# Detection_Circuit_Sheet_02.net
KiCad netlist of a schematic drawn in Altium Designer
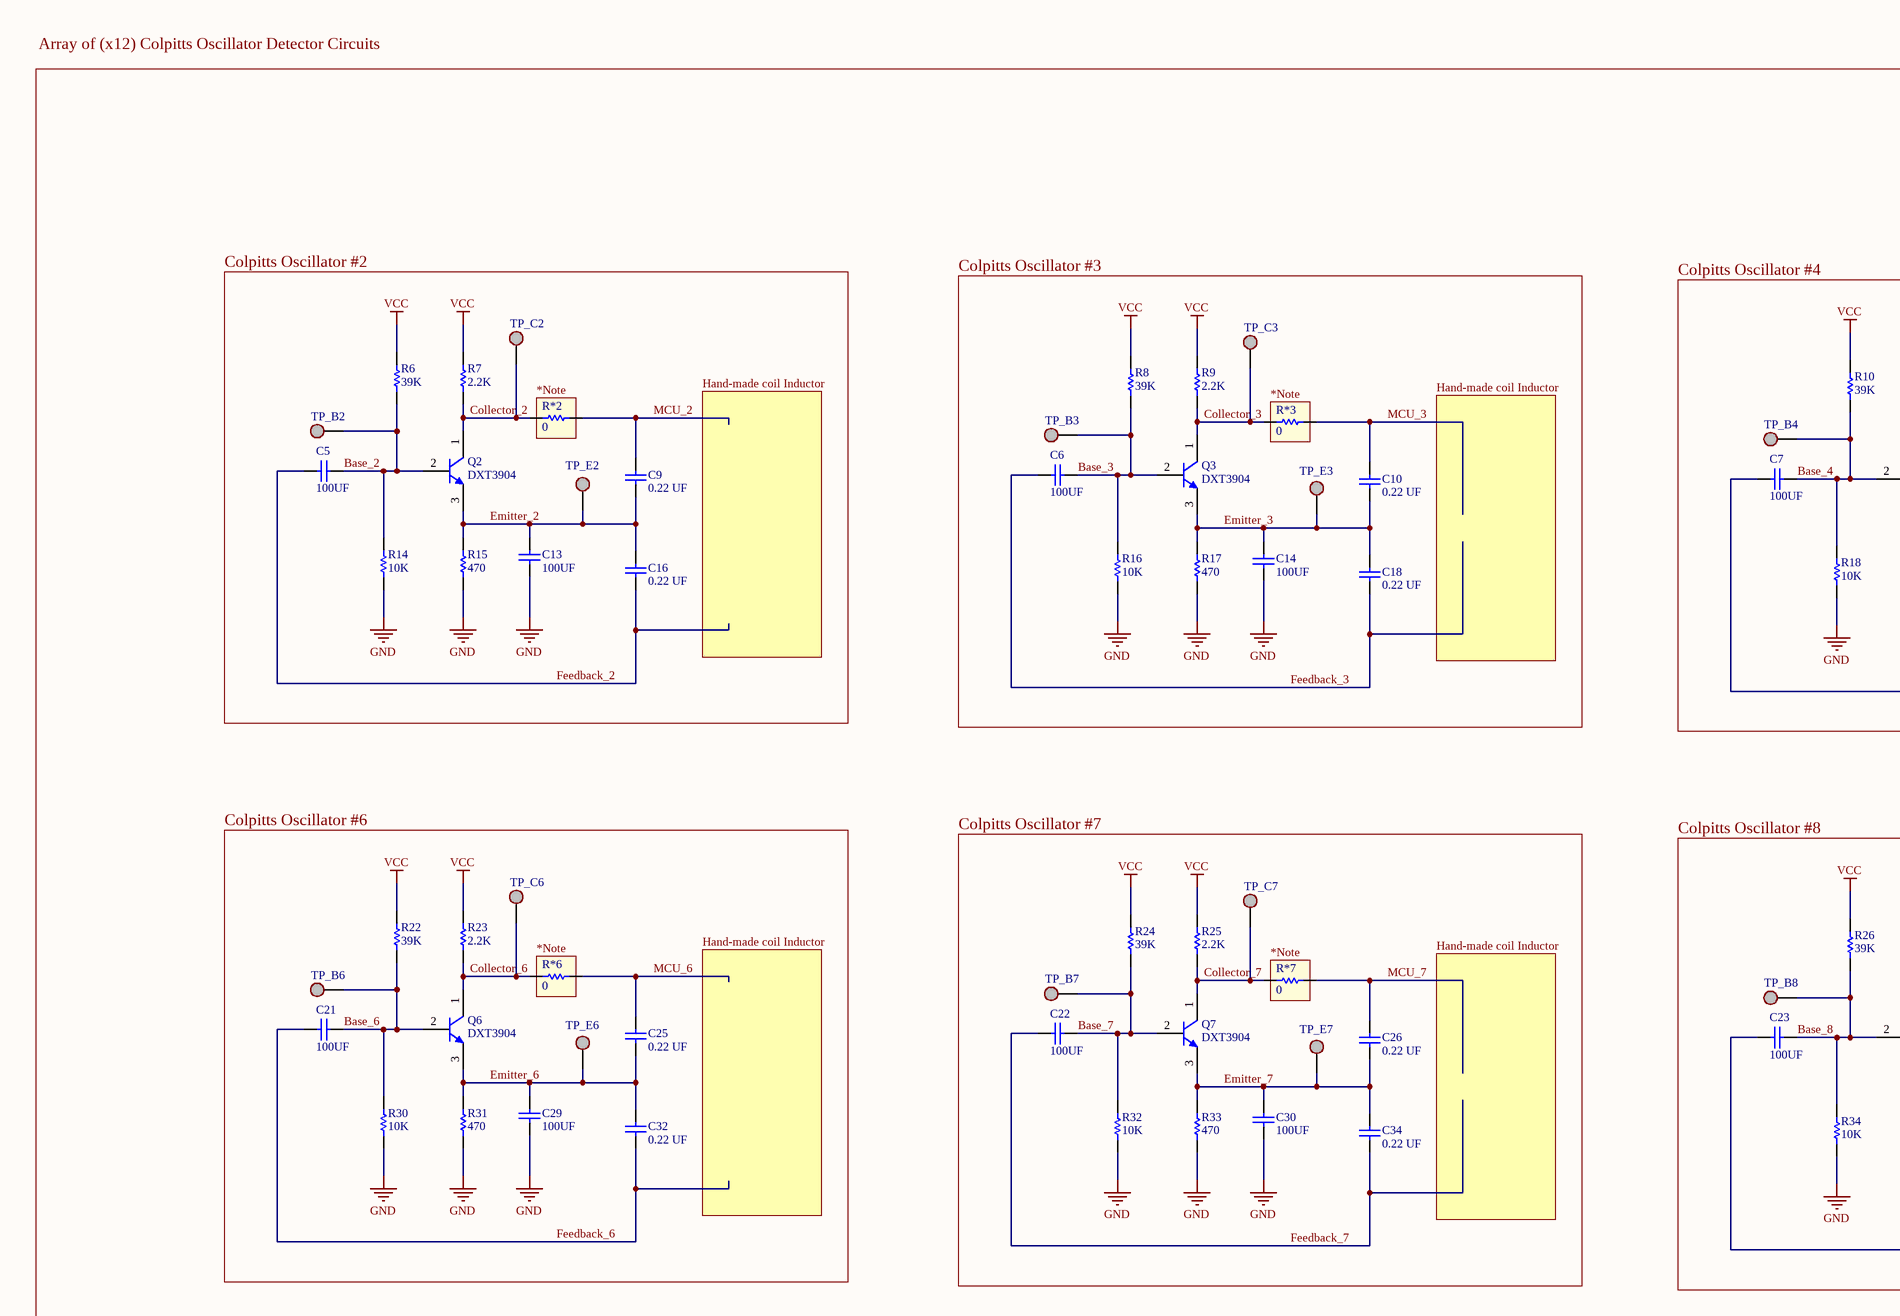
[diagram p0: Detection_Circuit_Sheet_02.SchDoc, top left]
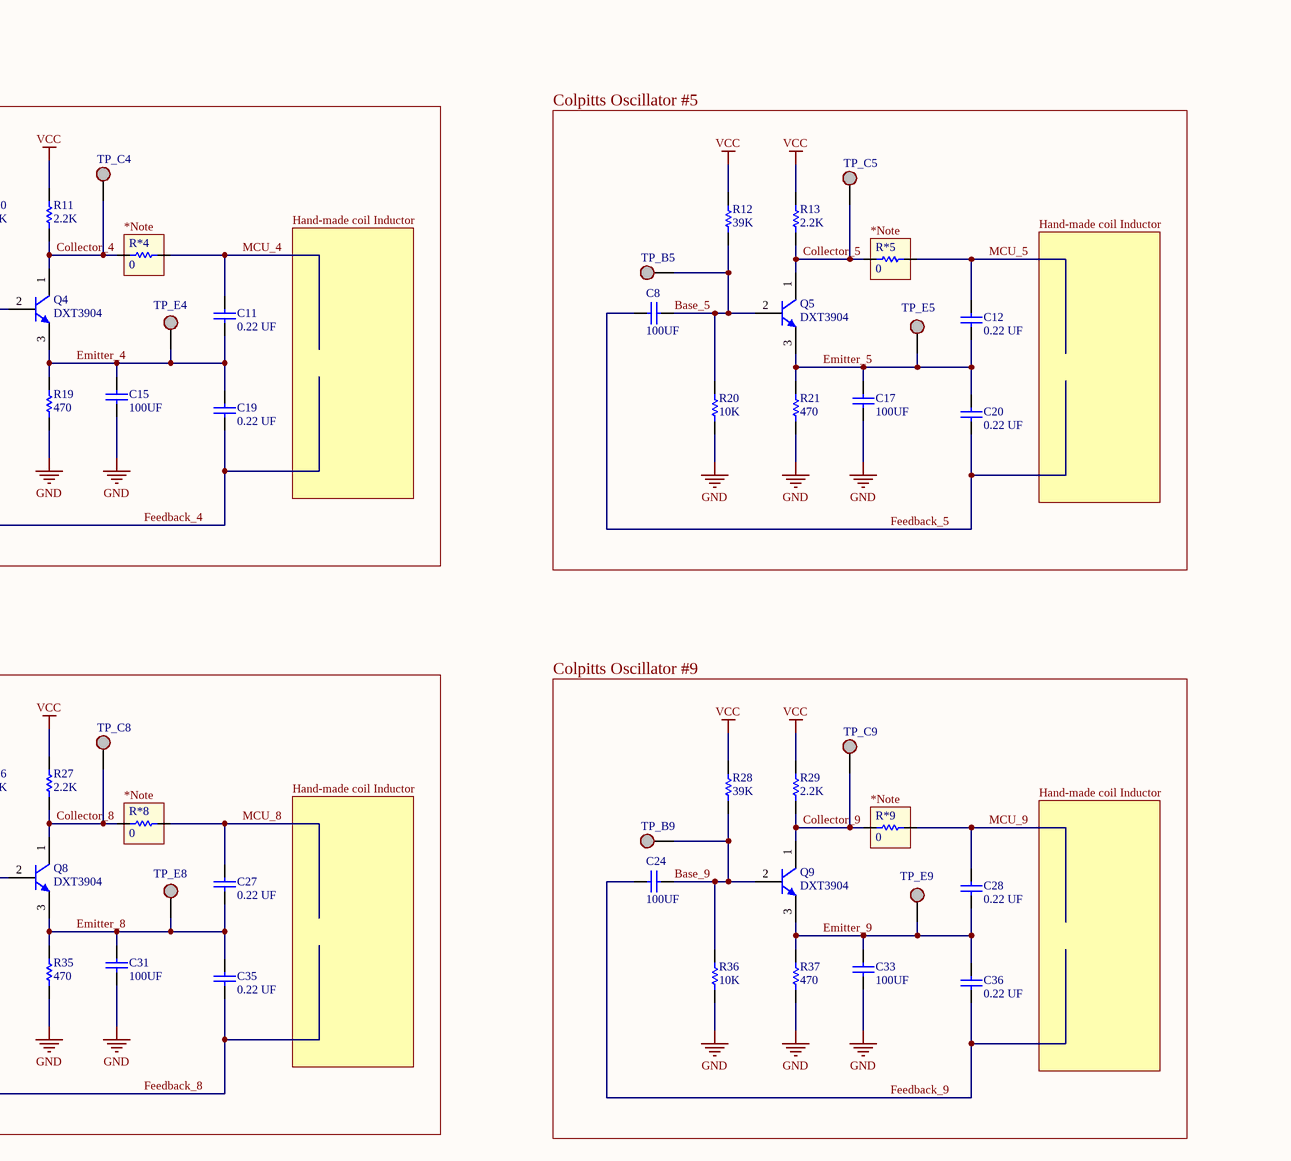
[diagram p1: Detection_Circuit_Sheet_02.SchDoc, top right]
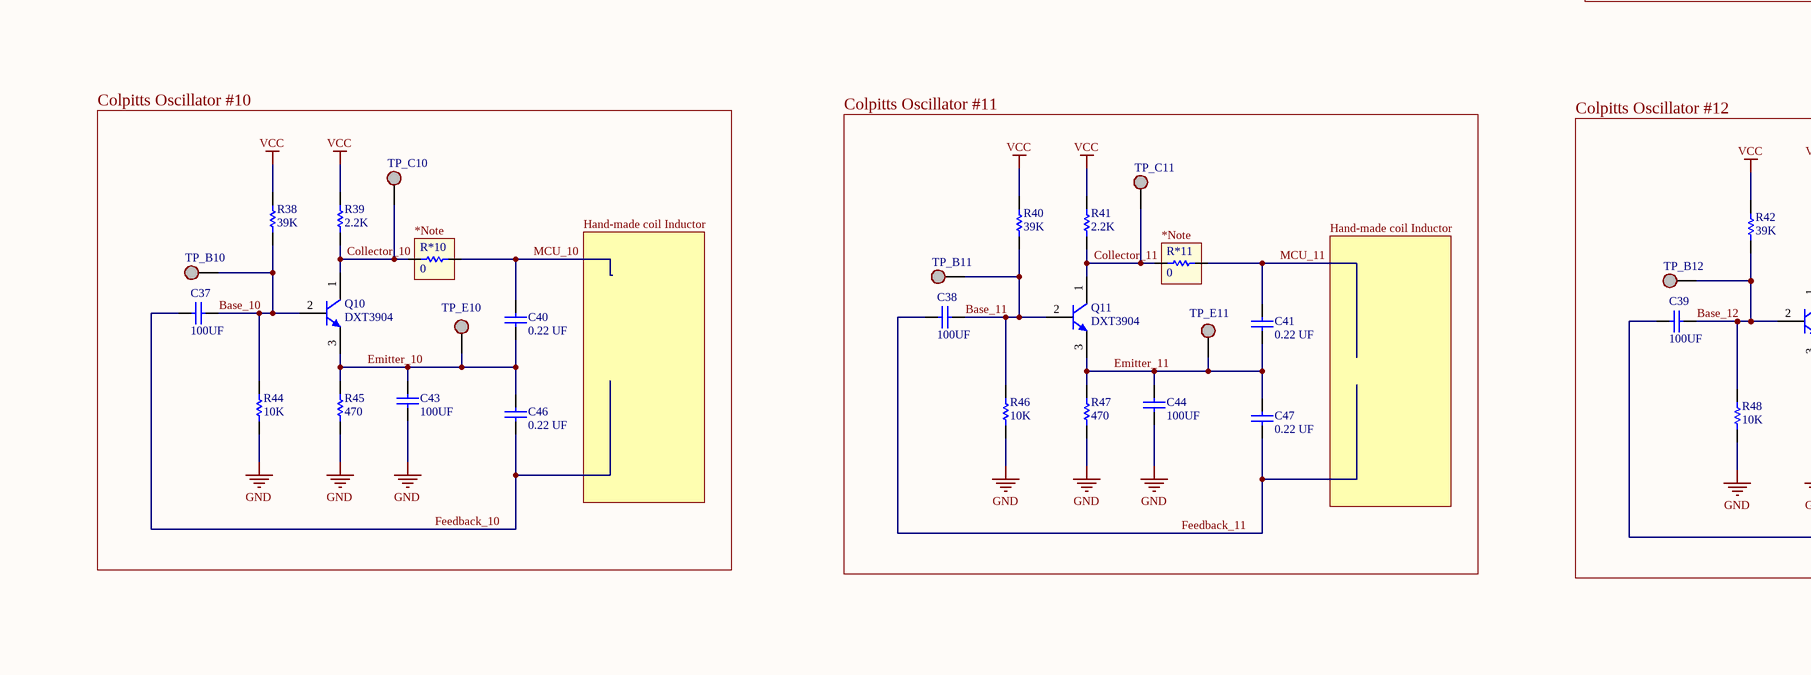
[diagram p2: Detection_Circuit_Sheet_02.SchDoc, bottom left]
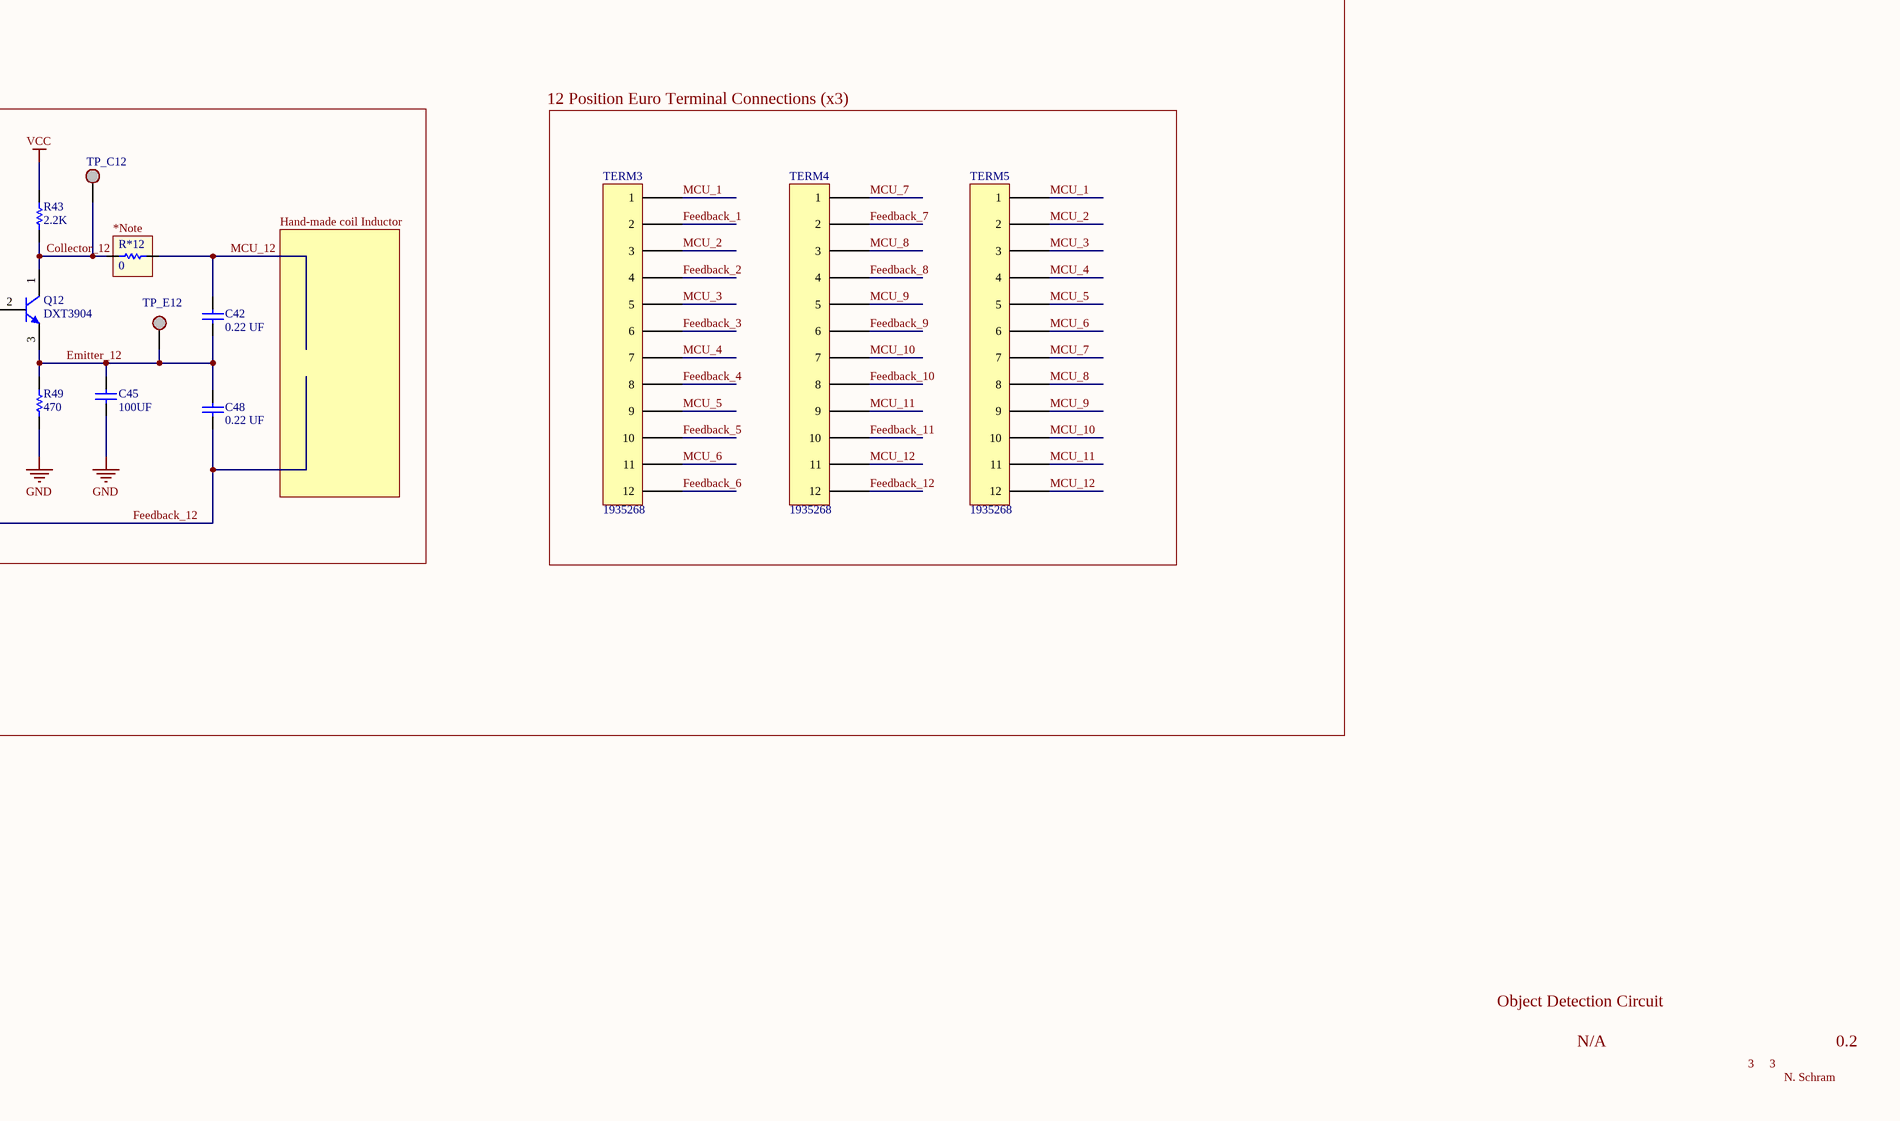
[diagram p3: Detection_Circuit_Sheet_02.SchDoc, bottom right]

(export (version "E")
  (design (tool "Eeschema 10.0.6"))
  (components
    (comp (ref "C5")
      (value "100UF")
      (footprint "C1210_M")
      (description "CAP CER 100UF 16V X5R 1210")
      (fields (field (name "MANUFACTURER PART NUMBER") "CC1210MKX5R7BB107") (field (name "TOLERANCE") "±20%"))
      (libsource (lib "CC1210MKX5R7BB107") (part "CC1210MKX5R7BB107"))
    )
    (comp (ref "C6")
      (value "100UF")
      (footprint "C1210_M")
      (description "CAP CER 100UF 16V X5R 1210")
      (fields (field (name "MANUFACTURER PART NUMBER") "CC1210MKX5R7BB107") (field (name "TOLERANCE") "±20%"))
      (libsource (lib "CC1210MKX5R7BB107") (part "CC1210MKX5R7BB107"))
    )
    (comp (ref "C7")
      (value "100UF")
      (footprint "C1210_M")
      (description "CAP CER 100UF 16V X5R 1210")
      (fields (field (name "MANUFACTURER PART NUMBER") "CC1210MKX5R7BB107") (field (name "TOLERANCE") "±20%"))
      (libsource (lib "CC1210MKX5R7BB107") (part "CC1210MKX5R7BB107"))
    )
    (comp (ref "C8")
      (value "100UF")
      (footprint "C1210_M")
      (description "CAP CER 100UF 16V X5R 1210")
      (fields (field (name "MANUFACTURER PART NUMBER") "CC1210MKX5R7BB107") (field (name "TOLERANCE") "±20%"))
      (libsource (lib "CC1210MKX5R7BB107") (part "CC1210MKX5R7BB107"))
    )
    (comp (ref "C9")
      (value "08055C224JAT2A")
      (footprint "6-0805_N")
      (description "CAP CER 0.22UF 50V X7R 0805")
      (fields
        (field (name "MANUFACTURER") "AVX Corporation")
        (field (name "TOLERANCE") "±5%")
        (field (name "CAPACITANCE") "0.22 UF")
      )
      (libsource (lib "08055C224JAT2A") (part "08055C224JAT2A"))
    )
    (comp (ref "C10")
      (value "08055C224JAT2A")
      (footprint "6-0805_N")
      (description "CAP CER 0.22UF 50V X7R 0805")
      (fields
        (field (name "MANUFACTURER") "AVX Corporation")
        (field (name "TOLERANCE") "±5%")
        (field (name "CAPACITANCE") "0.22 UF")
      )
      (libsource (lib "08055C224JAT2A") (part "08055C224JAT2A"))
    )
    (comp (ref "C11")
      (value "08055C224JAT2A")
      (footprint "6-0805_N")
      (description "CAP CER 0.22UF 50V X7R 0805")
      (fields
        (field (name "MANUFACTURER") "AVX Corporation")
        (field (name "TOLERANCE") "±5%")
        (field (name "CAPACITANCE") "0.22 UF")
      )
      (libsource (lib "08055C224JAT2A") (part "08055C224JAT2A"))
    )
    (comp (ref "C12")
      (value "08055C224JAT2A")
      (footprint "6-0805_N")
      (description "CAP CER 0.22UF 50V X7R 0805")
      (fields
        (field (name "MANUFACTURER") "AVX Corporation")
        (field (name "TOLERANCE") "±5%")
        (field (name "CAPACITANCE") "0.22 UF")
      )
      (libsource (lib "08055C224JAT2A") (part "08055C224JAT2A"))
    )
    (comp (ref "C13")
      (value "100UF")
      (footprint "C1210_M")
      (description "CAP CER 100UF 16V X5R 1210")
      (fields (field (name "MANUFACTURER PART NUMBER") "CC1210MKX5R7BB107") (field (name "TOLERANCE") "±20%"))
      (libsource (lib "CC1210MKX5R7BB107") (part "CC1210MKX5R7BB107"))
    )
    (comp (ref "C14")
      (value "100UF")
      (footprint "C1210_M")
      (description "CAP CER 100UF 16V X5R 1210")
      (fields (field (name "MANUFACTURER PART NUMBER") "CC1210MKX5R7BB107") (field (name "TOLERANCE") "±20%"))
      (libsource (lib "CC1210MKX5R7BB107") (part "CC1210MKX5R7BB107"))
    )
    (comp (ref "C15")
      (value "100UF")
      (footprint "C1210_M")
      (description "CAP CER 100UF 16V X5R 1210")
      (fields (field (name "MANUFACTURER PART NUMBER") "CC1210MKX5R7BB107") (field (name "TOLERANCE") "±20%"))
      (libsource (lib "CC1210MKX5R7BB107") (part "CC1210MKX5R7BB107"))
    )
    (comp (ref "C16")
      (value "08055C224JAT2A")
      (footprint "6-0805_N")
      (description "CAP CER 0.22UF 50V X7R 0805")
      (fields
        (field (name "MANUFACTURER") "AVX Corporation")
        (field (name "TOLERANCE") "±5%")
        (field (name "CAPACITANCE") "0.22 UF")
      )
      (libsource (lib "08055C224JAT2A") (part "08055C224JAT2A"))
    )
    (comp (ref "C17")
      (value "100UF")
      (footprint "C1210_M")
      (description "CAP CER 100UF 16V X5R 1210")
      (fields (field (name "MANUFACTURER PART NUMBER") "CC1210MKX5R7BB107") (field (name "TOLERANCE") "±20%"))
      (libsource (lib "CC1210MKX5R7BB107") (part "CC1210MKX5R7BB107"))
    )
    (comp (ref "C18")
      (value "08055C224JAT2A")
      (footprint "6-0805_N")
      (description "CAP CER 0.22UF 50V X7R 0805")
      (fields
        (field (name "MANUFACTURER") "AVX Corporation")
        (field (name "TOLERANCE") "±5%")
        (field (name "CAPACITANCE") "0.22 UF")
      )
      (libsource (lib "08055C224JAT2A") (part "08055C224JAT2A"))
    )
    (comp (ref "C19")
      (value "08055C224JAT2A")
      (footprint "6-0805_N")
      (description "CAP CER 0.22UF 50V X7R 0805")
      (fields
        (field (name "MANUFACTURER") "AVX Corporation")
        (field (name "TOLERANCE") "±5%")
        (field (name "CAPACITANCE") "0.22 UF")
      )
      (libsource (lib "08055C224JAT2A") (part "08055C224JAT2A"))
    )
    (comp (ref "C20")
      (value "08055C224JAT2A")
      (footprint "6-0805_N")
      (description "CAP CER 0.22UF 50V X7R 0805")
      (fields
        (field (name "MANUFACTURER") "AVX Corporation")
        (field (name "TOLERANCE") "±5%")
        (field (name "CAPACITANCE") "0.22 UF")
      )
      (libsource (lib "08055C224JAT2A") (part "08055C224JAT2A"))
    )
    (comp (ref "C21")
      (value "100UF")
      (footprint "C1210_M")
      (description "CAP CER 100UF 16V X5R 1210")
      (fields (field (name "MANUFACTURER PART NUMBER") "CC1210MKX5R7BB107") (field (name "TOLERANCE") "±20%"))
      (libsource (lib "CC1210MKX5R7BB107") (part "CC1210MKX5R7BB107"))
    )
    (comp (ref "C22")
      (value "100UF")
      (footprint "C1210_M")
      (description "CAP CER 100UF 16V X5R 1210")
      (fields (field (name "MANUFACTURER PART NUMBER") "CC1210MKX5R7BB107") (field (name "TOLERANCE") "±20%"))
      (libsource (lib "CC1210MKX5R7BB107") (part "CC1210MKX5R7BB107"))
    )
    (comp (ref "C23")
      (value "100UF")
      (footprint "C1210_M")
      (description "CAP CER 100UF 16V X5R 1210")
      (fields (field (name "MANUFACTURER PART NUMBER") "CC1210MKX5R7BB107") (field (name "TOLERANCE") "±20%"))
      (libsource (lib "CC1210MKX5R7BB107") (part "CC1210MKX5R7BB107"))
    )
    (comp (ref "C24")
      (value "100UF")
      (footprint "C1210_M")
      (description "CAP CER 100UF 16V X5R 1210")
      (fields (field (name "MANUFACTURER PART NUMBER") "CC1210MKX5R7BB107") (field (name "TOLERANCE") "±20%"))
      (libsource (lib "CC1210MKX5R7BB107") (part "CC1210MKX5R7BB107"))
    )
    (comp (ref "C25")
      (value "08055C224JAT2A")
      (footprint "6-0805_N")
      (description "CAP CER 0.22UF 50V X7R 0805")
      (fields
        (field (name "MANUFACTURER") "AVX Corporation")
        (field (name "TOLERANCE") "±5%")
        (field (name "CAPACITANCE") "0.22 UF")
      )
      (libsource (lib "08055C224JAT2A") (part "08055C224JAT2A"))
    )
    (comp (ref "C26")
      (value "08055C224JAT2A")
      (footprint "6-0805_N")
      (description "CAP CER 0.22UF 50V X7R 0805")
      (fields
        (field (name "MANUFACTURER") "AVX Corporation")
        (field (name "TOLERANCE") "±5%")
        (field (name "CAPACITANCE") "0.22 UF")
      )
      (libsource (lib "08055C224JAT2A") (part "08055C224JAT2A"))
    )
    (comp (ref "C27")
      (value "08055C224JAT2A")
      (footprint "6-0805_N")
      (description "CAP CER 0.22UF 50V X7R 0805")
      (fields
        (field (name "MANUFACTURER") "AVX Corporation")
        (field (name "TOLERANCE") "±5%")
        (field (name "CAPACITANCE") "0.22 UF")
      )
      (libsource (lib "08055C224JAT2A") (part "08055C224JAT2A"))
    )
    (comp (ref "C28")
      (value "08055C224JAT2A")
      (footprint "6-0805_N")
      (description "CAP CER 0.22UF 50V X7R 0805")
      (fields
        (field (name "MANUFACTURER") "AVX Corporation")
        (field (name "TOLERANCE") "±5%")
        (field (name "CAPACITANCE") "0.22 UF")
      )
      (libsource (lib "08055C224JAT2A") (part "08055C224JAT2A"))
    )
    (comp (ref "C29")
      (value "100UF")
      (footprint "C1210_M")
      (description "CAP CER 100UF 16V X5R 1210")
      (fields (field (name "MANUFACTURER PART NUMBER") "CC1210MKX5R7BB107") (field (name "TOLERANCE") "±20%"))
      (libsource (lib "CC1210MKX5R7BB107") (part "CC1210MKX5R7BB107"))
    )
    (comp (ref "C30")
      (value "100UF")
      (footprint "C1210_M")
      (description "CAP CER 100UF 16V X5R 1210")
      (fields (field (name "MANUFACTURER PART NUMBER") "CC1210MKX5R7BB107") (field (name "TOLERANCE") "±20%"))
      (libsource (lib "CC1210MKX5R7BB107") (part "CC1210MKX5R7BB107"))
    )
    (comp (ref "C31")
      (value "100UF")
      (footprint "C1210_M")
      (description "CAP CER 100UF 16V X5R 1210")
      (fields (field (name "MANUFACTURER PART NUMBER") "CC1210MKX5R7BB107") (field (name "TOLERANCE") "±20%"))
      (libsource (lib "CC1210MKX5R7BB107") (part "CC1210MKX5R7BB107"))
    )
    (comp (ref "C32")
      (value "08055C224JAT2A")
      (footprint "6-0805_N")
      (description "CAP CER 0.22UF 50V X7R 0805")
      (fields
        (field (name "MANUFACTURER") "AVX Corporation")
        (field (name "TOLERANCE") "±5%")
        (field (name "CAPACITANCE") "0.22 UF")
      )
      (libsource (lib "08055C224JAT2A") (part "08055C224JAT2A"))
    )
    (comp (ref "C33")
      (value "100UF")
      (footprint "C1210_M")
      (description "CAP CER 100UF 16V X5R 1210")
      (fields (field (name "MANUFACTURER PART NUMBER") "CC1210MKX5R7BB107") (field (name "TOLERANCE") "±20%"))
      (libsource (lib "CC1210MKX5R7BB107") (part "CC1210MKX5R7BB107"))
    )
    (comp (ref "C34")
      (value "08055C224JAT2A")
      (footprint "6-0805_N")
      (description "CAP CER 0.22UF 50V X7R 0805")
      (fields
        (field (name "MANUFACTURER") "AVX Corporation")
        (field (name "TOLERANCE") "±5%")
        (field (name "CAPACITANCE") "0.22 UF")
      )
      (libsource (lib "08055C224JAT2A") (part "08055C224JAT2A"))
    )
    (comp (ref "C35")
      (value "08055C224JAT2A")
      (footprint "6-0805_N")
      (description "CAP CER 0.22UF 50V X7R 0805")
      (fields
        (field (name "MANUFACTURER") "AVX Corporation")
        (field (name "TOLERANCE") "±5%")
        (field (name "CAPACITANCE") "0.22 UF")
      )
      (libsource (lib "08055C224JAT2A") (part "08055C224JAT2A"))
    )
    (comp (ref "C36")
      (value "08055C224JAT2A")
      (footprint "6-0805_N")
      (description "CAP CER 0.22UF 50V X7R 0805")
      (fields
        (field (name "MANUFACTURER") "AVX Corporation")
        (field (name "TOLERANCE") "±5%")
        (field (name "CAPACITANCE") "0.22 UF")
      )
      (libsource (lib "08055C224JAT2A") (part "08055C224JAT2A"))
    )
    (comp (ref "C37")
      (value "100UF")
      (footprint "C1210_M")
      (description "CAP CER 100UF 16V X5R 1210")
      (fields (field (name "MANUFACTURER PART NUMBER") "CC1210MKX5R7BB107") (field (name "TOLERANCE") "±20%"))
      (libsource (lib "CC1210MKX5R7BB107") (part "CC1210MKX5R7BB107"))
    )
    (comp (ref "C38")
      (value "100UF")
      (footprint "C1210_M")
      (description "CAP CER 100UF 16V X5R 1210")
      (fields (field (name "MANUFACTURER PART NUMBER") "CC1210MKX5R7BB107") (field (name "TOLERANCE") "±20%"))
      (libsource (lib "CC1210MKX5R7BB107") (part "CC1210MKX5R7BB107"))
    )
    (comp (ref "C39")
      (value "100UF")
      (footprint "C1210_M")
      (description "CAP CER 100UF 16V X5R 1210")
      (fields (field (name "MANUFACTURER PART NUMBER") "CC1210MKX5R7BB107") (field (name "TOLERANCE") "±20%"))
      (libsource (lib "CC1210MKX5R7BB107") (part "CC1210MKX5R7BB107"))
    )
    (comp (ref "C40")
      (value "08055C224JAT2A")
      (footprint "6-0805_N")
      (description "CAP CER 0.22UF 50V X7R 0805")
      (fields
        (field (name "MANUFACTURER") "AVX Corporation")
        (field (name "TOLERANCE") "±5%")
        (field (name "CAPACITANCE") "0.22 UF")
      )
      (libsource (lib "08055C224JAT2A") (part "08055C224JAT2A"))
    )
    (comp (ref "C41")
      (value "08055C224JAT2A")
      (footprint "6-0805_N")
      (description "CAP CER 0.22UF 50V X7R 0805")
      (fields
        (field (name "MANUFACTURER") "AVX Corporation")
        (field (name "TOLERANCE") "±5%")
        (field (name "CAPACITANCE") "0.22 UF")
      )
      (libsource (lib "08055C224JAT2A") (part "08055C224JAT2A"))
    )
    (comp (ref "C42")
      (value "08055C224JAT2A")
      (footprint "6-0805_N")
      (description "CAP CER 0.22UF 50V X7R 0805")
      (fields
        (field (name "MANUFACTURER") "AVX Corporation")
        (field (name "TOLERANCE") "±5%")
        (field (name "CAPACITANCE") "0.22 UF")
      )
      (libsource (lib "08055C224JAT2A") (part "08055C224JAT2A"))
    )
    (comp (ref "C43")
      (value "100UF")
      (footprint "C1210_M")
      (description "CAP CER 100UF 16V X5R 1210")
      (fields (field (name "MANUFACTURER PART NUMBER") "CC1210MKX5R7BB107") (field (name "TOLERANCE") "±20%"))
      (libsource (lib "CC1210MKX5R7BB107") (part "CC1210MKX5R7BB107"))
    )
    (comp (ref "C44")
      (value "100UF")
      (footprint "C1210_M")
      (description "CAP CER 100UF 16V X5R 1210")
      (fields (field (name "MANUFACTURER PART NUMBER") "CC1210MKX5R7BB107") (field (name "TOLERANCE") "±20%"))
      (libsource (lib "CC1210MKX5R7BB107") (part "CC1210MKX5R7BB107"))
    )
    (comp (ref "C45")
      (value "100UF")
      (footprint "C1210_M")
      (description "CAP CER 100UF 16V X5R 1210")
      (fields (field (name "MANUFACTURER PART NUMBER") "CC1210MKX5R7BB107") (field (name "TOLERANCE") "±20%"))
      (libsource (lib "CC1210MKX5R7BB107") (part "CC1210MKX5R7BB107"))
    )
    (comp (ref "C46")
      (value "08055C224JAT2A")
      (footprint "6-0805_N")
      (description "CAP CER 0.22UF 50V X7R 0805")
      (fields
        (field (name "MANUFACTURER") "AVX Corporation")
        (field (name "TOLERANCE") "±5%")
        (field (name "CAPACITANCE") "0.22 UF")
      )
      (libsource (lib "08055C224JAT2A") (part "08055C224JAT2A"))
    )
    (comp (ref "C47")
      (value "08055C224JAT2A")
      (footprint "6-0805_N")
      (description "CAP CER 0.22UF 50V X7R 0805")
      (fields
        (field (name "MANUFACTURER") "AVX Corporation")
        (field (name "TOLERANCE") "±5%")
        (field (name "CAPACITANCE") "0.22 UF")
      )
      (libsource (lib "08055C224JAT2A") (part "08055C224JAT2A"))
    )
    (comp (ref "C48")
      (value "08055C224JAT2A")
      (footprint "6-0805_N")
      (description "CAP CER 0.22UF 50V X7R 0805")
      (fields
        (field (name "MANUFACTURER") "AVX Corporation")
        (field (name "TOLERANCE") "±5%")
        (field (name "CAPACITANCE") "0.22 UF")
      )
      (libsource (lib "08055C224JAT2A") (part "08055C224JAT2A"))
    )
    (comp (ref "Q2")
      (value "DXT3904")
      (footprint "DXT3904-13")
      (description "TRANS NPN 40V 0.2A SOT89-3")
      (fields (field (name "MANUFACTURER PART NUMBER") "DXT3904-13") (field (name "MANUFACTURER") "Diodes"))
      (libsource (lib "DXT3904-13") (part "DXT3904-13"))
    )
    (comp (ref "Q3")
      (value "DXT3904")
      (footprint "DXT3904-13")
      (description "TRANS NPN 40V 0.2A SOT89-3")
      (fields (field (name "MANUFACTURER PART NUMBER") "DXT3904-13") (field (name "MANUFACTURER") "Diodes"))
      (libsource (lib "DXT3904-13") (part "DXT3904-13"))
    )
    (comp (ref "Q4")
      (value "DXT3904")
      (footprint "DXT3904-13")
      (description "TRANS NPN 40V 0.2A SOT89-3")
      (fields (field (name "MANUFACTURER PART NUMBER") "DXT3904-13") (field (name "MANUFACTURER") "Diodes"))
      (libsource (lib "DXT3904-13") (part "DXT3904-13"))
    )
    (comp (ref "Q5")
      (value "DXT3904")
      (footprint "DXT3904-13")
      (description "TRANS NPN 40V 0.2A SOT89-3")
      (fields (field (name "MANUFACTURER PART NUMBER") "DXT3904-13") (field (name "MANUFACTURER") "Diodes"))
      (libsource (lib "DXT3904-13") (part "DXT3904-13"))
    )
    (comp (ref "Q6")
      (value "DXT3904")
      (footprint "DXT3904-13")
      (description "TRANS NPN 40V 0.2A SOT89-3")
      (fields (field (name "MANUFACTURER PART NUMBER") "DXT3904-13") (field (name "MANUFACTURER") "Diodes"))
      (libsource (lib "DXT3904-13") (part "DXT3904-13"))
    )
    (comp (ref "Q7")
      (value "DXT3904")
      (footprint "DXT3904-13")
      (description "TRANS NPN 40V 0.2A SOT89-3")
      (fields (field (name "MANUFACTURER PART NUMBER") "DXT3904-13") (field (name "MANUFACTURER") "Diodes"))
      (libsource (lib "DXT3904-13") (part "DXT3904-13"))
    )
    (comp (ref "Q8")
      (value "DXT3904")
      (footprint "DXT3904-13")
      (description "TRANS NPN 40V 0.2A SOT89-3")
      (fields (field (name "MANUFACTURER PART NUMBER") "DXT3904-13") (field (name "MANUFACTURER") "Diodes"))
      (libsource (lib "DXT3904-13") (part "DXT3904-13"))
    )
    (comp (ref "Q9")
      (value "DXT3904")
      (footprint "DXT3904-13")
      (description "TRANS NPN 40V 0.2A SOT89-3")
      (fields (field (name "MANUFACTURER PART NUMBER") "DXT3904-13") (field (name "MANUFACTURER") "Diodes"))
      (libsource (lib "DXT3904-13") (part "DXT3904-13"))
    )
    (comp (ref "Q10")
      (value "DXT3904")
      (footprint "DXT3904-13")
      (description "TRANS NPN 40V 0.2A SOT89-3")
      (fields (field (name "MANUFACTURER PART NUMBER") "DXT3904-13") (field (name "MANUFACTURER") "Diodes"))
      (libsource (lib "DXT3904-13") (part "DXT3904-13"))
    )
    (comp (ref "Q11")
      (value "DXT3904")
      (footprint "DXT3904-13")
      (description "TRANS NPN 40V 0.2A SOT89-3")
      (fields (field (name "MANUFACTURER PART NUMBER") "DXT3904-13") (field (name "MANUFACTURER") "Diodes"))
      (libsource (lib "DXT3904-13") (part "DXT3904-13"))
    )
    (comp (ref "Q12")
      (value "DXT3904")
      (footprint "DXT3904-13")
      (description "TRANS NPN 40V 0.2A SOT89-3")
      (fields (field (name "MANUFACTURER PART NUMBER") "DXT3904-13") (field (name "MANUFACTURER") "Diodes"))
      (libsource (lib "DXT3904-13") (part "DXT3904-13"))
    )
    (comp (ref "R*2")
      (value "0")
      (footprint "6-0805_M")
      (description "RES SMD 0 OHM JUMPER 1/8W 0805")
      (fields
        (field (name "MANUFACTURER PART NUMBER") "ERJ-6GEY0R00V")
        (field (name "MANUFACTURER") "Panasonic ECG")
      )
      (libsource (lib "ERJ-6GEY0R00V") (part "ERJ-6GEY0R00V"))
    )
    (comp (ref "R*3")
      (value "0")
      (footprint "6-0805_M")
      (description "RES SMD 0 OHM JUMPER 1/8W 0805")
      (fields
        (field (name "MANUFACTURER PART NUMBER") "ERJ-6GEY0R00V")
        (field (name "MANUFACTURER") "Panasonic ECG")
      )
      (libsource (lib "ERJ-6GEY0R00V") (part "ERJ-6GEY0R00V"))
    )
    (comp (ref "R*4")
      (value "0")
      (footprint "6-0805_M")
      (description "RES SMD 0 OHM JUMPER 1/8W 0805")
      (fields
        (field (name "MANUFACTURER PART NUMBER") "ERJ-6GEY0R00V")
        (field (name "MANUFACTURER") "Panasonic ECG")
      )
      (libsource (lib "ERJ-6GEY0R00V") (part "ERJ-6GEY0R00V"))
    )
    (comp (ref "R*5")
      (value "0")
      (footprint "6-0805_M")
      (description "RES SMD 0 OHM JUMPER 1/8W 0805")
      (fields
        (field (name "MANUFACTURER PART NUMBER") "ERJ-6GEY0R00V")
        (field (name "MANUFACTURER") "Panasonic ECG")
      )
      (libsource (lib "ERJ-6GEY0R00V") (part "ERJ-6GEY0R00V"))
    )
    (comp (ref "R*6")
      (value "0")
      (footprint "6-0805_M")
      (description "RES SMD 0 OHM JUMPER 1/8W 0805")
      (fields
        (field (name "MANUFACTURER PART NUMBER") "ERJ-6GEY0R00V")
        (field (name "MANUFACTURER") "Panasonic ECG")
      )
      (libsource (lib "ERJ-6GEY0R00V") (part "ERJ-6GEY0R00V"))
    )
    (comp (ref "R*7")
      (value "0")
      (footprint "6-0805_M")
      (description "RES SMD 0 OHM JUMPER 1/8W 0805")
      (fields
        (field (name "MANUFACTURER PART NUMBER") "ERJ-6GEY0R00V")
        (field (name "MANUFACTURER") "Panasonic ECG")
      )
      (libsource (lib "ERJ-6GEY0R00V") (part "ERJ-6GEY0R00V"))
    )
    (comp (ref "R*8")
      (value "0")
      (footprint "6-0805_M")
      (description "RES SMD 0 OHM JUMPER 1/8W 0805")
      (fields
        (field (name "MANUFACTURER PART NUMBER") "ERJ-6GEY0R00V")
        (field (name "MANUFACTURER") "Panasonic ECG")
      )
      (libsource (lib "ERJ-6GEY0R00V") (part "ERJ-6GEY0R00V"))
    )
    (comp (ref "R*9")
      (value "0")
      (footprint "6-0805_M")
      (description "RES SMD 0 OHM JUMPER 1/8W 0805")
      (fields
        (field (name "MANUFACTURER PART NUMBER") "ERJ-6GEY0R00V")
        (field (name "MANUFACTURER") "Panasonic ECG")
      )
      (libsource (lib "ERJ-6GEY0R00V") (part "ERJ-6GEY0R00V"))
    )
    (comp (ref "R*10")
      (value "0")
      (footprint "6-0805_M")
      (description "RES SMD 0 OHM JUMPER 1/8W 0805")
      (fields
        (field (name "MANUFACTURER PART NUMBER") "ERJ-6GEY0R00V")
        (field (name "MANUFACTURER") "Panasonic ECG")
      )
      (libsource (lib "ERJ-6GEY0R00V") (part "ERJ-6GEY0R00V"))
    )
    (comp (ref "R*11")
      (value "0")
      (footprint "6-0805_M")
      (description "RES SMD 0 OHM JUMPER 1/8W 0805")
      (fields
        (field (name "MANUFACTURER PART NUMBER") "ERJ-6GEY0R00V")
        (field (name "MANUFACTURER") "Panasonic ECG")
      )
      (libsource (lib "ERJ-6GEY0R00V") (part "ERJ-6GEY0R00V"))
    )
    (comp (ref "R*12")
      (value "0")
      (footprint "6-0805_M")
      (description "RES SMD 0 OHM JUMPER 1/8W 0805")
      (fields
        (field (name "MANUFACTURER PART NUMBER") "ERJ-6GEY0R00V")
        (field (name "MANUFACTURER") "Panasonic ECG")
      )
      (libsource (lib "ERJ-6GEY0R00V") (part "ERJ-6GEY0R00V"))
    )
    (comp (ref "R6")
      (value "39K")
      (footprint "6-0805_M")
      (description "RES SMD 39K OHM 0.5% 1/4W 0805")
      (fields (field (name "MANUFACTURER PART NUMBER") "ERJ-PB6D3902V") (field (name "TOLERANCE") "±0.5%"))
      (libsource (lib "ERJ-PB6D3902V") (part "ERJ-PB6D3902V"))
    )
    (comp (ref "R7")
      (value "2.2K")
      (footprint "6-0805_M")
      (description "RES SMD 2.2K OHM 0.5% 1/4W 0805")
      (fields (field (name "MANUFACTURER PART NUMBER") "ERJ-PB6D2201V") (field (name "TOLERANCE") "±0.5%"))
      (libsource (lib "ERJ-PB6D2201V") (part "ERJ-PB6D2201V"))
    )
    (comp (ref "R8")
      (value "39K")
      (footprint "6-0805_M")
      (description "RES SMD 39K OHM 0.5% 1/4W 0805")
      (fields (field (name "MANUFACTURER PART NUMBER") "ERJ-PB6D3902V") (field (name "TOLERANCE") "±0.5%"))
      (libsource (lib "ERJ-PB6D3902V") (part "ERJ-PB6D3902V"))
    )
    (comp (ref "R9")
      (value "2.2K")
      (footprint "6-0805_M")
      (description "RES SMD 2.2K OHM 0.5% 1/4W 0805")
      (fields (field (name "MANUFACTURER PART NUMBER") "ERJ-PB6D2201V") (field (name "TOLERANCE") "±0.5%"))
      (libsource (lib "ERJ-PB6D2201V") (part "ERJ-PB6D2201V"))
    )
    (comp (ref "R10")
      (value "39K")
      (footprint "6-0805_M")
      (description "RES SMD 39K OHM 0.5% 1/4W 0805")
      (fields (field (name "MANUFACTURER PART NUMBER") "ERJ-PB6D3902V") (field (name "TOLERANCE") "±0.5%"))
      (libsource (lib "ERJ-PB6D3902V") (part "ERJ-PB6D3902V"))
    )
    (comp (ref "R11")
      (value "2.2K")
      (footprint "6-0805_M")
      (description "RES SMD 2.2K OHM 0.5% 1/4W 0805")
      (fields (field (name "MANUFACTURER PART NUMBER") "ERJ-PB6D2201V") (field (name "TOLERANCE") "±0.5%"))
      (libsource (lib "ERJ-PB6D2201V") (part "ERJ-PB6D2201V"))
    )
    (comp (ref "R12")
      (value "39K")
      (footprint "6-0805_M")
      (description "RES SMD 39K OHM 0.5% 1/4W 0805")
      (fields (field (name "MANUFACTURER PART NUMBER") "ERJ-PB6D3902V") (field (name "TOLERANCE") "±0.5%"))
      (libsource (lib "ERJ-PB6D3902V") (part "ERJ-PB6D3902V"))
    )
    (comp (ref "R13")
      (value "2.2K")
      (footprint "6-0805_M")
      (description "RES SMD 2.2K OHM 0.5% 1/4W 0805")
      (fields (field (name "MANUFACTURER PART NUMBER") "ERJ-PB6D2201V") (field (name "TOLERANCE") "±0.5%"))
      (libsource (lib "ERJ-PB6D2201V") (part "ERJ-PB6D2201V"))
    )
    (comp (ref "R14")
      (value "10K")
      (footprint "6-0805_M")
      (description "RES SMD 10K OHM 1% 1/4W 0805")
      (fields (field (name "MANUFACTURER PART NUMBER") "RNCP0805FTD10K0") (field (name "TOLERANCE") "±1%"))
      (libsource (lib "RNCP0805FTD10K0") (part "RNCP0805FTD10K0"))
    )
    (comp (ref "R15")
      (value "470")
      (footprint "6-0805_M")
      (description "RES SMD 470 OHM 0.5% 1/4W 0805")
      (fields (field (name "MANUFACTURER PART NUMBER") "ERJ-PB6D4700V") (field (name "TOLERANCE") "±0.5%"))
      (libsource (lib "ERJ-PB6D4700V") (part "ERJ-PB6D4700V"))
    )
    (comp (ref "R16")
      (value "10K")
      (footprint "6-0805_M")
      (description "RES SMD 10K OHM 1% 1/4W 0805")
      (fields (field (name "MANUFACTURER PART NUMBER") "RNCP0805FTD10K0") (field (name "TOLERANCE") "±1%"))
      (libsource (lib "RNCP0805FTD10K0") (part "RNCP0805FTD10K0"))
    )
    (comp (ref "R17")
      (value "470")
      (footprint "6-0805_M")
      (description "RES SMD 470 OHM 0.5% 1/4W 0805")
      (fields (field (name "MANUFACTURER PART NUMBER") "ERJ-PB6D4700V") (field (name "TOLERANCE") "±0.5%"))
      (libsource (lib "ERJ-PB6D4700V") (part "ERJ-PB6D4700V"))
    )
    (comp (ref "R18")
      (value "10K")
      (footprint "6-0805_M")
      (description "RES SMD 10K OHM 1% 1/4W 0805")
      (fields (field (name "MANUFACTURER PART NUMBER") "RNCP0805FTD10K0") (field (name "TOLERANCE") "±1%"))
      (libsource (lib "RNCP0805FTD10K0") (part "RNCP0805FTD10K0"))
    )
    (comp (ref "R19")
      (value "470")
      (footprint "6-0805_M")
      (description "RES SMD 470 OHM 0.5% 1/4W 0805")
      (fields (field (name "MANUFACTURER PART NUMBER") "ERJ-PB6D4700V") (field (name "TOLERANCE") "±0.5%"))
      (libsource (lib "ERJ-PB6D4700V") (part "ERJ-PB6D4700V"))
    )
    (comp (ref "R20")
      (value "10K")
      (footprint "6-0805_M")
      (description "RES SMD 10K OHM 1% 1/4W 0805")
      (fields (field (name "MANUFACTURER PART NUMBER") "RNCP0805FTD10K0") (field (name "TOLERANCE") "±1%"))
      (libsource (lib "RNCP0805FTD10K0") (part "RNCP0805FTD10K0"))
    )
    (comp (ref "R21")
      (value "470")
      (footprint "6-0805_M")
      (description "RES SMD 470 OHM 0.5% 1/4W 0805")
      (fields (field (name "MANUFACTURER PART NUMBER") "ERJ-PB6D4700V") (field (name "TOLERANCE") "±0.5%"))
      (libsource (lib "ERJ-PB6D4700V") (part "ERJ-PB6D4700V"))
    )
    (comp (ref "R22")
      (value "39K")
      (footprint "6-0805_M")
      (description "RES SMD 39K OHM 0.5% 1/4W 0805")
      (fields (field (name "MANUFACTURER PART NUMBER") "ERJ-PB6D3902V") (field (name "TOLERANCE") "±0.5%"))
      (libsource (lib "ERJ-PB6D3902V") (part "ERJ-PB6D3902V"))
    )
    (comp (ref "R23")
      (value "2.2K")
      (footprint "6-0805_M")
      (description "RES SMD 2.2K OHM 0.5% 1/4W 0805")
      (fields (field (name "MANUFACTURER PART NUMBER") "ERJ-PB6D2201V") (field (name "TOLERANCE") "±0.5%"))
      (libsource (lib "ERJ-PB6D2201V") (part "ERJ-PB6D2201V"))
    )
    (comp (ref "R24")
      (value "39K")
      (footprint "6-0805_M")
      (description "RES SMD 39K OHM 0.5% 1/4W 0805")
      (fields (field (name "MANUFACTURER PART NUMBER") "ERJ-PB6D3902V") (field (name "TOLERANCE") "±0.5%"))
      (libsource (lib "ERJ-PB6D3902V") (part "ERJ-PB6D3902V"))
    )
    (comp (ref "R25")
      (value "2.2K")
      (footprint "6-0805_M")
      (description "RES SMD 2.2K OHM 0.5% 1/4W 0805")
      (fields (field (name "MANUFACTURER PART NUMBER") "ERJ-PB6D2201V") (field (name "TOLERANCE") "±0.5%"))
      (libsource (lib "ERJ-PB6D2201V") (part "ERJ-PB6D2201V"))
    )
    (comp (ref "R26")
      (value "39K")
      (footprint "6-0805_M")
      (description "RES SMD 39K OHM 0.5% 1/4W 0805")
      (fields (field (name "MANUFACTURER PART NUMBER") "ERJ-PB6D3902V") (field (name "TOLERANCE") "±0.5%"))
      (libsource (lib "ERJ-PB6D3902V") (part "ERJ-PB6D3902V"))
    )
    (comp (ref "R27")
      (value "2.2K")
      (footprint "6-0805_M")
      (description "RES SMD 2.2K OHM 0.5% 1/4W 0805")
      (fields (field (name "MANUFACTURER PART NUMBER") "ERJ-PB6D2201V") (field (name "TOLERANCE") "±0.5%"))
      (libsource (lib "ERJ-PB6D2201V") (part "ERJ-PB6D2201V"))
    )
    (comp (ref "R28")
      (value "39K")
      (footprint "6-0805_M")
      (description "RES SMD 39K OHM 0.5% 1/4W 0805")
      (fields (field (name "MANUFACTURER PART NUMBER") "ERJ-PB6D3902V") (field (name "TOLERANCE") "±0.5%"))
      (libsource (lib "ERJ-PB6D3902V") (part "ERJ-PB6D3902V"))
    )
    (comp (ref "R29")
      (value "2.2K")
      (footprint "6-0805_M")
      (description "RES SMD 2.2K OHM 0.5% 1/4W 0805")
      (fields (field (name "MANUFACTURER PART NUMBER") "ERJ-PB6D2201V") (field (name "TOLERANCE") "±0.5%"))
      (libsource (lib "ERJ-PB6D2201V") (part "ERJ-PB6D2201V"))
    )
    (comp (ref "R30")
      (value "10K")
      (footprint "6-0805_M")
      (description "RES SMD 10K OHM 1% 1/4W 0805")
      (fields (field (name "MANUFACTURER PART NUMBER") "RNCP0805FTD10K0") (field (name "TOLERANCE") "±1%"))
      (libsource (lib "RNCP0805FTD10K0") (part "RNCP0805FTD10K0"))
    )
    (comp (ref "R31")
      (value "470")
      (footprint "6-0805_M")
      (description "RES SMD 470 OHM 0.5% 1/4W 0805")
      (fields (field (name "MANUFACTURER PART NUMBER") "ERJ-PB6D4700V") (field (name "TOLERANCE") "±0.5%"))
      (libsource (lib "ERJ-PB6D4700V") (part "ERJ-PB6D4700V"))
    )
    (comp (ref "R32")
      (value "10K")
      (footprint "6-0805_M")
      (description "RES SMD 10K OHM 1% 1/4W 0805")
      (fields (field (name "MANUFACTURER PART NUMBER") "RNCP0805FTD10K0") (field (name "TOLERANCE") "±1%"))
      (libsource (lib "RNCP0805FTD10K0") (part "RNCP0805FTD10K0"))
    )
    (comp (ref "R33")
      (value "470")
      (footprint "6-0805_M")
      (description "RES SMD 470 OHM 0.5% 1/4W 0805")
      (fields (field (name "MANUFACTURER PART NUMBER") "ERJ-PB6D4700V") (field (name "TOLERANCE") "±0.5%"))
      (libsource (lib "ERJ-PB6D4700V") (part "ERJ-PB6D4700V"))
    )
    (comp (ref "R34")
      (value "10K")
      (footprint "6-0805_M")
      (description "RES SMD 10K OHM 1% 1/4W 0805")
      (fields (field (name "MANUFACTURER PART NUMBER") "RNCP0805FTD10K0") (field (name "TOLERANCE") "±1%"))
      (libsource (lib "RNCP0805FTD10K0") (part "RNCP0805FTD10K0"))
    )
    (comp (ref "R35")
      (value "470")
      (footprint "6-0805_M")
      (description "RES SMD 470 OHM 0.5% 1/4W 0805")
      (fields (field (name "MANUFACTURER PART NUMBER") "ERJ-PB6D4700V") (field (name "TOLERANCE") "±0.5%"))
      (libsource (lib "ERJ-PB6D4700V") (part "ERJ-PB6D4700V"))
    )
    (comp (ref "R36")
      (value "10K")
      (footprint "6-0805_M")
      (description "RES SMD 10K OHM 1% 1/4W 0805")
      (fields (field (name "MANUFACTURER PART NUMBER") "RNCP0805FTD10K0") (field (name "TOLERANCE") "±1%"))
      (libsource (lib "RNCP0805FTD10K0") (part "RNCP0805FTD10K0"))
    )
    (comp (ref "R37")
      (value "470")
      (footprint "6-0805_M")
      (description "RES SMD 470 OHM 0.5% 1/4W 0805")
      (fields (field (name "MANUFACTURER PART NUMBER") "ERJ-PB6D4700V") (field (name "TOLERANCE") "±0.5%"))
      (libsource (lib "ERJ-PB6D4700V") (part "ERJ-PB6D4700V"))
    )
    (comp (ref "R38")
      (value "39K")
      (footprint "6-0805_M")
      (description "RES SMD 39K OHM 0.5% 1/4W 0805")
      (fields (field (name "MANUFACTURER PART NUMBER") "ERJ-PB6D3902V") (field (name "TOLERANCE") "±0.5%"))
      (libsource (lib "ERJ-PB6D3902V") (part "ERJ-PB6D3902V"))
    )
    (comp (ref "R39")
      (value "2.2K")
      (footprint "6-0805_M")
      (description "RES SMD 2.2K OHM 0.5% 1/4W 0805")
      (fields (field (name "MANUFACTURER PART NUMBER") "ERJ-PB6D2201V") (field (name "TOLERANCE") "±0.5%"))
      (libsource (lib "ERJ-PB6D2201V") (part "ERJ-PB6D2201V"))
    )
    (comp (ref "R40")
      (value "39K")
      (footprint "6-0805_M")
      (description "RES SMD 39K OHM 0.5% 1/4W 0805")
      (fields (field (name "MANUFACTURER PART NUMBER") "ERJ-PB6D3902V") (field (name "TOLERANCE") "±0.5%"))
      (libsource (lib "ERJ-PB6D3902V") (part "ERJ-PB6D3902V"))
    )
    (comp (ref "R41")
      (value "2.2K")
      (footprint "6-0805_M")
      (description "RES SMD 2.2K OHM 0.5% 1/4W 0805")
      (fields (field (name "MANUFACTURER PART NUMBER") "ERJ-PB6D2201V") (field (name "TOLERANCE") "±0.5%"))
      (libsource (lib "ERJ-PB6D2201V") (part "ERJ-PB6D2201V"))
    )
    (comp (ref "R42")
      (value "39K")
      (footprint "6-0805_M")
      (description "RES SMD 39K OHM 0.5% 1/4W 0805")
      (fields (field (name "MANUFACTURER PART NUMBER") "ERJ-PB6D3902V") (field (name "TOLERANCE") "±0.5%"))
      (libsource (lib "ERJ-PB6D3902V") (part "ERJ-PB6D3902V"))
    )
    (comp (ref "R43")
      (value "2.2K")
      (footprint "6-0805_M")
      (description "RES SMD 2.2K OHM 0.5% 1/4W 0805")
      (fields (field (name "MANUFACTURER PART NUMBER") "ERJ-PB6D2201V") (field (name "TOLERANCE") "±0.5%"))
      (libsource (lib "ERJ-PB6D2201V") (part "ERJ-PB6D2201V"))
    )
    (comp (ref "R44")
      (value "10K")
      (footprint "6-0805_M")
      (description "RES SMD 10K OHM 1% 1/4W 0805")
      (fields (field (name "MANUFACTURER PART NUMBER") "RNCP0805FTD10K0") (field (name "TOLERANCE") "±1%"))
      (libsource (lib "RNCP0805FTD10K0") (part "RNCP0805FTD10K0"))
    )
    (comp (ref "R45")
      (value "470")
      (footprint "6-0805_M")
      (description "RES SMD 470 OHM 0.5% 1/4W 0805")
      (fields (field (name "MANUFACTURER PART NUMBER") "ERJ-PB6D4700V") (field (name "TOLERANCE") "±0.5%"))
      (libsource (lib "ERJ-PB6D4700V") (part "ERJ-PB6D4700V"))
    )
    (comp (ref "R46")
      (value "10K")
      (footprint "6-0805_M")
      (description "RES SMD 10K OHM 1% 1/4W 0805")
      (fields (field (name "MANUFACTURER PART NUMBER") "RNCP0805FTD10K0") (field (name "TOLERANCE") "±1%"))
      (libsource (lib "RNCP0805FTD10K0") (part "RNCP0805FTD10K0"))
    )
    (comp (ref "R47")
      (value "470")
      (footprint "6-0805_M")
      (description "RES SMD 470 OHM 0.5% 1/4W 0805")
      (fields (field (name "MANUFACTURER PART NUMBER") "ERJ-PB6D4700V") (field (name "TOLERANCE") "±0.5%"))
      (libsource (lib "ERJ-PB6D4700V") (part "ERJ-PB6D4700V"))
    )
    (comp (ref "R48")
      (value "10K")
      (footprint "6-0805_M")
      (description "RES SMD 10K OHM 1% 1/4W 0805")
      (fields (field (name "MANUFACTURER PART NUMBER") "RNCP0805FTD10K0") (field (name "TOLERANCE") "±1%"))
      (libsource (lib "RNCP0805FTD10K0") (part "RNCP0805FTD10K0"))
    )
    (comp (ref "R49")
      (value "470")
      (footprint "6-0805_M")
      (description "RES SMD 470 OHM 0.5% 1/4W 0805")
      (fields (field (name "MANUFACTURER PART NUMBER") "ERJ-PB6D4700V") (field (name "TOLERANCE") "±0.5%"))
      (libsource (lib "ERJ-PB6D4700V") (part "ERJ-PB6D4700V"))
    )
    (comp (ref "TERM3")
      (value "1935268")
      (footprint "1935268")
      (description "TERM BLOCK PCB 12POS 5.0MM GREEN")
      (fields (field (name "MANUFACTURER") "Phoenix Contact"))
      (libsource (lib "1935268") (part "1935268"))
    )
    (comp (ref "TERM4")
      (value "1935268")
      (footprint "1935268")
      (description "TERM BLOCK PCB 12POS 5.0MM GREEN")
      (fields (field (name "MANUFACTURER") "Phoenix Contact"))
      (libsource (lib "1935268") (part "1935268"))
    )
    (comp (ref "TERM5")
      (value "1935268")
      (footprint "1935268")
      (description "TERM BLOCK PCB 12POS 5.0MM GREEN")
      (fields (field (name "MANUFACTURER") "Phoenix Contact"))
      (libsource (lib "1935268") (part "1935268"))
    )
    (comp (ref "TP_B2")
      (value "TestPoint")
      (footprint "TestPoint")
      (description "Test Point")
      (libsource (lib "TestPoint") (part "TestPoint"))
    )
    (comp (ref "TP_B3")
      (value "TestPoint")
      (footprint "TestPoint")
      (description "Test Point")
      (libsource (lib "TestPoint") (part "TestPoint"))
    )
    (comp (ref "TP_B4")
      (value "TestPoint")
      (footprint "TestPoint")
      (description "Test Point")
      (libsource (lib "TestPoint") (part "TestPoint"))
    )
    (comp (ref "TP_B5")
      (value "TestPoint")
      (footprint "TestPoint")
      (description "Test Point")
      (libsource (lib "TestPoint") (part "TestPoint"))
    )
    (comp (ref "TP_B6")
      (value "TestPoint")
      (footprint "TestPoint")
      (description "Test Point")
      (libsource (lib "TestPoint") (part "TestPoint"))
    )
    (comp (ref "TP_B7")
      (value "TestPoint")
      (footprint "TestPoint")
      (description "Test Point")
      (libsource (lib "TestPoint") (part "TestPoint"))
    )
    (comp (ref "TP_B8")
      (value "TestPoint")
      (footprint "TestPoint")
      (description "Test Point")
      (libsource (lib "TestPoint") (part "TestPoint"))
    )
    (comp (ref "TP_B9")
      (value "TestPoint")
      (footprint "TestPoint")
      (description "Test Point")
      (libsource (lib "TestPoint") (part "TestPoint"))
    )
    (comp (ref "TP_B10")
      (value "TestPoint")
      (footprint "TestPoint")
      (description "Test Point")
      (libsource (lib "TestPoint") (part "TestPoint"))
    )
    (comp (ref "TP_B11")
      (value "TestPoint")
      (footprint "TestPoint")
      (description "Test Point")
      (libsource (lib "TestPoint") (part "TestPoint"))
    )
    (comp (ref "TP_B12")
      (value "TestPoint")
      (footprint "TestPoint")
      (description "Test Point")
      (libsource (lib "TestPoint") (part "TestPoint"))
    )
    (comp (ref "TP_C2")
      (value "TestPoint")
      (footprint "TestPoint")
      (description "Test Point")
      (libsource (lib "TestPoint") (part "TestPoint"))
    )
    (comp (ref "TP_C3")
      (value "TestPoint")
      (footprint "TestPoint")
      (description "Test Point")
      (libsource (lib "TestPoint") (part "TestPoint"))
    )
    (comp (ref "TP_C4")
      (value "TestPoint")
      (footprint "TestPoint")
      (description "Test Point")
      (libsource (lib "TestPoint") (part "TestPoint"))
    )
    (comp (ref "TP_C5")
      (value "TestPoint")
      (footprint "TestPoint")
      (description "Test Point")
      (libsource (lib "TestPoint") (part "TestPoint"))
    )
    (comp (ref "TP_C6")
      (value "TestPoint")
      (footprint "TestPoint")
      (description "Test Point")
      (libsource (lib "TestPoint") (part "TestPoint"))
    )
    (comp (ref "TP_C7")
      (value "TestPoint")
      (footprint "TestPoint")
      (description "Test Point")
      (libsource (lib "TestPoint") (part "TestPoint"))
    )
    (comp (ref "TP_C8")
      (value "TestPoint")
      (footprint "TestPoint")
      (description "Test Point")
      (libsource (lib "TestPoint") (part "TestPoint"))
    )
    (comp (ref "TP_C9")
      (value "TestPoint")
      (footprint "TestPoint")
      (description "Test Point")
      (libsource (lib "TestPoint") (part "TestPoint"))
    )
    (comp (ref "TP_C10")
      (value "TestPoint")
      (footprint "TestPoint")
      (description "Test Point")
      (libsource (lib "TestPoint") (part "TestPoint"))
    )
    (comp (ref "TP_C11")
      (value "TestPoint")
      (footprint "TestPoint")
      (description "Test Point")
      (libsource (lib "TestPoint") (part "TestPoint"))
    )
    (comp (ref "TP_C12")
      (value "TestPoint")
      (footprint "TestPoint")
      (description "Test Point")
      (libsource (lib "TestPoint") (part "TestPoint"))
    )
    (comp (ref "TP_E2")
      (value "TestPoint")
      (footprint "TestPoint")
      (description "Test Point")
      (libsource (lib "TestPoint") (part "TestPoint"))
    )
    (comp (ref "TP_E3")
      (value "TestPoint")
      (footprint "TestPoint")
      (description "Test Point")
      (libsource (lib "TestPoint") (part "TestPoint"))
    )
    (comp (ref "TP_E4")
      (value "TestPoint")
      (footprint "TestPoint")
      (description "Test Point")
      (libsource (lib "TestPoint") (part "TestPoint"))
    )
    (comp (ref "TP_E5")
      (value "TestPoint")
      (footprint "TestPoint")
      (description "Test Point")
      (libsource (lib "TestPoint") (part "TestPoint"))
    )
    (comp (ref "TP_E6")
      (value "TestPoint")
      (footprint "TestPoint")
      (description "Test Point")
      (libsource (lib "TestPoint") (part "TestPoint"))
    )
    (comp (ref "TP_E7")
      (value "TestPoint")
      (footprint "TestPoint")
      (description "Test Point")
      (libsource (lib "TestPoint") (part "TestPoint"))
    )
    (comp (ref "TP_E8")
      (value "TestPoint")
      (footprint "TestPoint")
      (description "Test Point")
      (libsource (lib "TestPoint") (part "TestPoint"))
    )
    (comp (ref "TP_E9")
      (value "TestPoint")
      (footprint "TestPoint")
      (description "Test Point")
      (libsource (lib "TestPoint") (part "TestPoint"))
    )
    (comp (ref "TP_E10")
      (value "TestPoint")
      (footprint "TestPoint")
      (description "Test Point")
      (libsource (lib "TestPoint") (part "TestPoint"))
    )
    (comp (ref "TP_E11")
      (value "TestPoint")
      (footprint "TestPoint")
      (description "Test Point")
      (libsource (lib "TestPoint") (part "TestPoint"))
    )
    (comp (ref "TP_E12")
      (value "TestPoint")
      (footprint "TestPoint")
      (description "Test Point")
      (libsource (lib "TestPoint") (part "TestPoint"))
    )
  )
  (nets
    (net (code "1") (name "/Base_2") (class "Default")
      (node (ref "C5") (pin "2") (pinfunction "2_2") (pintype "passive"))
      (node (ref "Q2") (pin "2") (pinfunction "B_2") (pintype "passive"))
      (node (ref "R14") (pin "2") (pinfunction "2_2") (pintype "passive"))
      (node (ref "R6") (pin "1") (pinfunction "1_1") (pintype "passive"))
      (node (ref "TP_B2") (pin "1") (pinfunction "1_1") (pintype "passive"))
    )
    (net (code "2") (name "/Base_3") (class "Default")
      (node (ref "C6") (pin "2") (pinfunction "2_2") (pintype "passive"))
      (node (ref "Q3") (pin "2") (pinfunction "B_2") (pintype "passive"))
      (node (ref "R16") (pin "2") (pinfunction "2_2") (pintype "passive"))
      (node (ref "R8") (pin "1") (pinfunction "1_1") (pintype "passive"))
      (node (ref "TP_B3") (pin "1") (pinfunction "1_1") (pintype "passive"))
    )
    (net (code "3") (name "/Base_4") (class "Default")
      (node (ref "C7") (pin "2") (pinfunction "2_2") (pintype "passive"))
      (node (ref "Q4") (pin "2") (pinfunction "B_2") (pintype "passive"))
      (node (ref "R10") (pin "1") (pinfunction "1_1") (pintype "passive"))
      (node (ref "R18") (pin "2") (pinfunction "2_2") (pintype "passive"))
      (node (ref "TP_B4") (pin "1") (pinfunction "1_1") (pintype "passive"))
    )
    (net (code "4") (name "/Base_5") (class "Default")
      (node (ref "C8") (pin "2") (pinfunction "2_2") (pintype "passive"))
      (node (ref "Q5") (pin "2") (pinfunction "B_2") (pintype "passive"))
      (node (ref "R12") (pin "1") (pinfunction "1_1") (pintype "passive"))
      (node (ref "R20") (pin "2") (pinfunction "2_2") (pintype "passive"))
      (node (ref "TP_B5") (pin "1") (pinfunction "1_1") (pintype "passive"))
    )
    (net (code "5") (name "/Base_6") (class "Default")
      (node (ref "C21") (pin "2") (pinfunction "2_2") (pintype "passive"))
      (node (ref "Q6") (pin "2") (pinfunction "B_2") (pintype "passive"))
      (node (ref "R22") (pin "1") (pinfunction "1_1") (pintype "passive"))
      (node (ref "R30") (pin "2") (pinfunction "2_2") (pintype "passive"))
      (node (ref "TP_B6") (pin "1") (pinfunction "1_1") (pintype "passive"))
    )
    (net (code "6") (name "/Base_7") (class "Default")
      (node (ref "C22") (pin "2") (pinfunction "2_2") (pintype "passive"))
      (node (ref "Q7") (pin "2") (pinfunction "B_2") (pintype "passive"))
      (node (ref "R24") (pin "1") (pinfunction "1_1") (pintype "passive"))
      (node (ref "R32") (pin "2") (pinfunction "2_2") (pintype "passive"))
      (node (ref "TP_B7") (pin "1") (pinfunction "1_1") (pintype "passive"))
    )
    (net (code "7") (name "/Base_8") (class "Default")
      (node (ref "C23") (pin "2") (pinfunction "2_2") (pintype "passive"))
      (node (ref "Q8") (pin "2") (pinfunction "B_2") (pintype "passive"))
      (node (ref "R26") (pin "1") (pinfunction "1_1") (pintype "passive"))
      (node (ref "R34") (pin "2") (pinfunction "2_2") (pintype "passive"))
      (node (ref "TP_B8") (pin "1") (pinfunction "1_1") (pintype "passive"))
    )
    (net (code "8") (name "/Base_9") (class "Default")
      (node (ref "C24") (pin "2") (pinfunction "2_2") (pintype "passive"))
      (node (ref "Q9") (pin "2") (pinfunction "B_2") (pintype "passive"))
      (node (ref "R28") (pin "1") (pinfunction "1_1") (pintype "passive"))
      (node (ref "R36") (pin "2") (pinfunction "2_2") (pintype "passive"))
      (node (ref "TP_B9") (pin "1") (pinfunction "1_1") (pintype "passive"))
    )
    (net (code "9") (name "/Base_10") (class "Default")
      (node (ref "C37") (pin "2") (pinfunction "2_2") (pintype "passive"))
      (node (ref "Q10") (pin "2") (pinfunction "B_2") (pintype "passive"))
      (node (ref "R38") (pin "1") (pinfunction "1_1") (pintype "passive"))
      (node (ref "R44") (pin "2") (pinfunction "2_2") (pintype "passive"))
      (node (ref "TP_B10") (pin "1") (pinfunction "1_1") (pintype "passive"))
    )
    (net (code "10") (name "/Base_11") (class "Default")
      (node (ref "C38") (pin "2") (pinfunction "2_2") (pintype "passive"))
      (node (ref "Q11") (pin "2") (pinfunction "B_2") (pintype "passive"))
      (node (ref "R40") (pin "1") (pinfunction "1_1") (pintype "passive"))
      (node (ref "R46") (pin "2") (pinfunction "2_2") (pintype "passive"))
      (node (ref "TP_B11") (pin "1") (pinfunction "1_1") (pintype "passive"))
    )
    (net (code "11") (name "/Base_12") (class "Default")
      (node (ref "C39") (pin "2") (pinfunction "2_2") (pintype "passive"))
      (node (ref "Q12") (pin "2") (pinfunction "B_2") (pintype "passive"))
      (node (ref "R42") (pin "1") (pinfunction "1_1") (pintype "passive"))
      (node (ref "R48") (pin "2") (pinfunction "2_2") (pintype "passive"))
      (node (ref "TP_B12") (pin "1") (pinfunction "1_1") (pintype "passive"))
    )
    (net (code "12") (name "/Collector_2") (class "Default")
      (node (ref "Q2") (pin "1") (pinfunction "C_1") (pintype "passive"))
      (node (ref "R*2") (pin "1") (pinfunction "1_1") (pintype "passive"))
      (node (ref "R7") (pin "1") (pinfunction "1_1") (pintype "passive"))
      (node (ref "TP_C2") (pin "1") (pinfunction "1_1") (pintype "passive"))
    )
    (net (code "13") (name "/Collector_3") (class "Default")
      (node (ref "Q3") (pin "1") (pinfunction "C_1") (pintype "passive"))
      (node (ref "R*3") (pin "1") (pinfunction "1_1") (pintype "passive"))
      (node (ref "R9") (pin "1") (pinfunction "1_1") (pintype "passive"))
      (node (ref "TP_C3") (pin "1") (pinfunction "1_1") (pintype "passive"))
    )
    (net (code "14") (name "/Collector_4") (class "Default")
      (node (ref "Q4") (pin "1") (pinfunction "C_1") (pintype "passive"))
      (node (ref "R*4") (pin "1") (pinfunction "1_1") (pintype "passive"))
      (node (ref "R11") (pin "1") (pinfunction "1_1") (pintype "passive"))
      (node (ref "TP_C4") (pin "1") (pinfunction "1_1") (pintype "passive"))
    )
    (net (code "15") (name "/Collector_5") (class "Default")
      (node (ref "Q5") (pin "1") (pinfunction "C_1") (pintype "passive"))
      (node (ref "R*5") (pin "1") (pinfunction "1_1") (pintype "passive"))
      (node (ref "R13") (pin "1") (pinfunction "1_1") (pintype "passive"))
      (node (ref "TP_C5") (pin "1") (pinfunction "1_1") (pintype "passive"))
    )
    (net (code "16") (name "/Collector_6") (class "Default")
      (node (ref "Q6") (pin "1") (pinfunction "C_1") (pintype "passive"))
      (node (ref "R*6") (pin "1") (pinfunction "1_1") (pintype "passive"))
      (node (ref "R23") (pin "1") (pinfunction "1_1") (pintype "passive"))
      (node (ref "TP_C6") (pin "1") (pinfunction "1_1") (pintype "passive"))
    )
    (net (code "17") (name "/Collector_7") (class "Default")
      (node (ref "Q7") (pin "1") (pinfunction "C_1") (pintype "passive"))
      (node (ref "R*7") (pin "1") (pinfunction "1_1") (pintype "passive"))
      (node (ref "R25") (pin "1") (pinfunction "1_1") (pintype "passive"))
      (node (ref "TP_C7") (pin "1") (pinfunction "1_1") (pintype "passive"))
    )
    (net (code "18") (name "/Collector_8") (class "Default")
      (node (ref "Q8") (pin "1") (pinfunction "C_1") (pintype "passive"))
      (node (ref "R*8") (pin "1") (pinfunction "1_1") (pintype "passive"))
      (node (ref "R27") (pin "1") (pinfunction "1_1") (pintype "passive"))
      (node (ref "TP_C8") (pin "1") (pinfunction "1_1") (pintype "passive"))
    )
    (net (code "19") (name "/Collector_9") (class "Default")
      (node (ref "Q9") (pin "1") (pinfunction "C_1") (pintype "passive"))
      (node (ref "R*9") (pin "1") (pinfunction "1_1") (pintype "passive"))
      (node (ref "R29") (pin "1") (pinfunction "1_1") (pintype "passive"))
      (node (ref "TP_C9") (pin "1") (pinfunction "1_1") (pintype "passive"))
    )
    (net (code "20") (name "/Collector_10") (class "Default")
      (node (ref "Q10") (pin "1") (pinfunction "C_1") (pintype "passive"))
      (node (ref "R*10") (pin "1") (pinfunction "1_1") (pintype "passive"))
      (node (ref "R39") (pin "1") (pinfunction "1_1") (pintype "passive"))
      (node (ref "TP_C10") (pin "1") (pinfunction "1_1") (pintype "passive"))
    )
    (net (code "21") (name "/Collector_11") (class "Default")
      (node (ref "Q11") (pin "1") (pinfunction "C_1") (pintype "passive"))
      (node (ref "R*11") (pin "1") (pinfunction "1_1") (pintype "passive"))
      (node (ref "R41") (pin "1") (pinfunction "1_1") (pintype "passive"))
      (node (ref "TP_C11") (pin "1") (pinfunction "1_1") (pintype "passive"))
    )
    (net (code "22") (name "/Collector_12") (class "Default")
      (node (ref "Q12") (pin "1") (pinfunction "C_1") (pintype "passive"))
      (node (ref "R*12") (pin "1") (pinfunction "1_1") (pintype "passive"))
      (node (ref "R43") (pin "1") (pinfunction "1_1") (pintype "passive"))
      (node (ref "TP_C12") (pin "1") (pinfunction "1_1") (pintype "passive"))
    )
    (net (code "23") (name "/Emitter_2") (class "Default")
      (node (ref "C13") (pin "2") (pinfunction "2_2") (pintype "passive"))
      (node (ref "C16") (pin "2") (pinfunction "2_2") (pintype "passive"))
      (node (ref "C9") (pin "1") (pinfunction "1_1") (pintype "passive"))
      (node (ref "Q2") (pin "3") (pinfunction "E_3") (pintype "passive"))
      (node (ref "R15") (pin "2") (pinfunction "2_2") (pintype "passive"))
      (node (ref "TP_E2") (pin "1") (pinfunction "1_1") (pintype "passive"))
    )
    (net (code "24") (name "/Emitter_3") (class "Default")
      (node (ref "C10") (pin "1") (pinfunction "1_1") (pintype "passive"))
      (node (ref "C14") (pin "2") (pinfunction "2_2") (pintype "passive"))
      (node (ref "C18") (pin "2") (pinfunction "2_2") (pintype "passive"))
      (node (ref "Q3") (pin "3") (pinfunction "E_3") (pintype "passive"))
      (node (ref "R17") (pin "2") (pinfunction "2_2") (pintype "passive"))
      (node (ref "TP_E3") (pin "1") (pinfunction "1_1") (pintype "passive"))
    )
    (net (code "25") (name "/Emitter_4") (class "Default")
      (node (ref "C11") (pin "1") (pinfunction "1_1") (pintype "passive"))
      (node (ref "C15") (pin "2") (pinfunction "2_2") (pintype "passive"))
      (node (ref "C19") (pin "2") (pinfunction "2_2") (pintype "passive"))
      (node (ref "Q4") (pin "3") (pinfunction "E_3") (pintype "passive"))
      (node (ref "R19") (pin "2") (pinfunction "2_2") (pintype "passive"))
      (node (ref "TP_E4") (pin "1") (pinfunction "1_1") (pintype "passive"))
    )
    (net (code "26") (name "/Emitter_5") (class "Default")
      (node (ref "C12") (pin "1") (pinfunction "1_1") (pintype "passive"))
      (node (ref "C17") (pin "2") (pinfunction "2_2") (pintype "passive"))
      (node (ref "C20") (pin "2") (pinfunction "2_2") (pintype "passive"))
      (node (ref "Q5") (pin "3") (pinfunction "E_3") (pintype "passive"))
      (node (ref "R21") (pin "2") (pinfunction "2_2") (pintype "passive"))
      (node (ref "TP_E5") (pin "1") (pinfunction "1_1") (pintype "passive"))
    )
    (net (code "27") (name "/Emitter_6") (class "Default")
      (node (ref "C25") (pin "1") (pinfunction "1_1") (pintype "passive"))
      (node (ref "C29") (pin "2") (pinfunction "2_2") (pintype "passive"))
      (node (ref "C32") (pin "2") (pinfunction "2_2") (pintype "passive"))
      (node (ref "Q6") (pin "3") (pinfunction "E_3") (pintype "passive"))
      (node (ref "R31") (pin "2") (pinfunction "2_2") (pintype "passive"))
      (node (ref "TP_E6") (pin "1") (pinfunction "1_1") (pintype "passive"))
    )
    (net (code "28") (name "/Emitter_7") (class "Default")
      (node (ref "C26") (pin "1") (pinfunction "1_1") (pintype "passive"))
      (node (ref "C30") (pin "2") (pinfunction "2_2") (pintype "passive"))
      (node (ref "C34") (pin "2") (pinfunction "2_2") (pintype "passive"))
      (node (ref "Q7") (pin "3") (pinfunction "E_3") (pintype "passive"))
      (node (ref "R33") (pin "2") (pinfunction "2_2") (pintype "passive"))
      (node (ref "TP_E7") (pin "1") (pinfunction "1_1") (pintype "passive"))
    )
    (net (code "29") (name "/Emitter_8") (class "Default")
      (node (ref "C27") (pin "1") (pinfunction "1_1") (pintype "passive"))
      (node (ref "C31") (pin "2") (pinfunction "2_2") (pintype "passive"))
      (node (ref "C35") (pin "2") (pinfunction "2_2") (pintype "passive"))
      (node (ref "Q8") (pin "3") (pinfunction "E_3") (pintype "passive"))
      (node (ref "R35") (pin "2") (pinfunction "2_2") (pintype "passive"))
      (node (ref "TP_E8") (pin "1") (pinfunction "1_1") (pintype "passive"))
    )
    (net (code "30") (name "/Emitter_9") (class "Default")
      (node (ref "C28") (pin "1") (pinfunction "1_1") (pintype "passive"))
      (node (ref "C33") (pin "2") (pinfunction "2_2") (pintype "passive"))
      (node (ref "C36") (pin "2") (pinfunction "2_2") (pintype "passive"))
      (node (ref "Q9") (pin "3") (pinfunction "E_3") (pintype "passive"))
      (node (ref "R37") (pin "2") (pinfunction "2_2") (pintype "passive"))
      (node (ref "TP_E9") (pin "1") (pinfunction "1_1") (pintype "passive"))
    )
    (net (code "31") (name "/Emitter_10") (class "Default")
      (node (ref "C40") (pin "1") (pinfunction "1_1") (pintype "passive"))
      (node (ref "C43") (pin "2") (pinfunction "2_2") (pintype "passive"))
      (node (ref "C46") (pin "2") (pinfunction "2_2") (pintype "passive"))
      (node (ref "Q10") (pin "3") (pinfunction "E_3") (pintype "passive"))
      (node (ref "R45") (pin "2") (pinfunction "2_2") (pintype "passive"))
      (node (ref "TP_E10") (pin "1") (pinfunction "1_1") (pintype "passive"))
    )
    (net (code "32") (name "/Emitter_11") (class "Default")
      (node (ref "C41") (pin "1") (pinfunction "1_1") (pintype "passive"))
      (node (ref "C44") (pin "2") (pinfunction "2_2") (pintype "passive"))
      (node (ref "C47") (pin "2") (pinfunction "2_2") (pintype "passive"))
      (node (ref "Q11") (pin "3") (pinfunction "E_3") (pintype "passive"))
      (node (ref "R47") (pin "2") (pinfunction "2_2") (pintype "passive"))
      (node (ref "TP_E11") (pin "1") (pinfunction "1_1") (pintype "passive"))
    )
    (net (code "33") (name "/Emitter_12") (class "Default")
      (node (ref "C42") (pin "1") (pinfunction "1_1") (pintype "passive"))
      (node (ref "C45") (pin "2") (pinfunction "2_2") (pintype "passive"))
      (node (ref "C48") (pin "2") (pinfunction "2_2") (pintype "passive"))
      (node (ref "Q12") (pin "3") (pinfunction "E_3") (pintype "passive"))
      (node (ref "R49") (pin "2") (pinfunction "2_2") (pintype "passive"))
      (node (ref "TP_E12") (pin "1") (pinfunction "1_1") (pintype "passive"))
    )
    (net (code "34") (name "/Feedback_1") (class "Default")
      (node (ref "TERM3") (pin "2") (pinfunction "2_2") (pintype "passive"))
    )
    (net (code "35") (name "/Feedback_2") (class "Default")
      (node (ref "C16") (pin "1") (pinfunction "1_1") (pintype "passive"))
      (node (ref "C5") (pin "1") (pinfunction "1_1") (pintype "passive"))
      (node (ref "TERM3") (pin "4") (pinfunction "4_4") (pintype "passive"))
    )
    (net (code "36") (name "/Feedback_3") (class "Default")
      (node (ref "C18") (pin "1") (pinfunction "1_1") (pintype "passive"))
      (node (ref "C6") (pin "1") (pinfunction "1_1") (pintype "passive"))
      (node (ref "TERM3") (pin "6") (pinfunction "6_6") (pintype "passive"))
    )
    (net (code "37") (name "/Feedback_4") (class "Default")
      (node (ref "C19") (pin "1") (pinfunction "1_1") (pintype "passive"))
      (node (ref "C7") (pin "1") (pinfunction "1_1") (pintype "passive"))
      (node (ref "TERM3") (pin "8") (pinfunction "8_8") (pintype "passive"))
    )
    (net (code "38") (name "/Feedback_5") (class "Default")
      (node (ref "C20") (pin "1") (pinfunction "1_1") (pintype "passive"))
      (node (ref "C8") (pin "1") (pinfunction "1_1") (pintype "passive"))
      (node (ref "TERM3") (pin "10") (pinfunction "10_10") (pintype "passive"))
    )
    (net (code "39") (name "/Feedback_6") (class "Default")
      (node (ref "C21") (pin "1") (pinfunction "1_1") (pintype "passive"))
      (node (ref "C32") (pin "1") (pinfunction "1_1") (pintype "passive"))
      (node (ref "TERM3") (pin "12") (pinfunction "12_12") (pintype "passive"))
    )
    (net (code "40") (name "/Feedback_7") (class "Default")
      (node (ref "C22") (pin "1") (pinfunction "1_1") (pintype "passive"))
      (node (ref "C34") (pin "1") (pinfunction "1_1") (pintype "passive"))
      (node (ref "TERM4") (pin "2") (pinfunction "2_2") (pintype "passive"))
    )
    (net (code "41") (name "/Feedback_8") (class "Default")
      (node (ref "C23") (pin "1") (pinfunction "1_1") (pintype "passive"))
      (node (ref "C35") (pin "1") (pinfunction "1_1") (pintype "passive"))
      (node (ref "TERM4") (pin "4") (pinfunction "4_4") (pintype "passive"))
    )
    (net (code "42") (name "/Feedback_9") (class "Default")
      (node (ref "C24") (pin "1") (pinfunction "1_1") (pintype "passive"))
      (node (ref "C36") (pin "1") (pinfunction "1_1") (pintype "passive"))
      (node (ref "TERM4") (pin "6") (pinfunction "6_6") (pintype "passive"))
    )
    (net (code "43") (name "/Feedback_10") (class "Default")
      (node (ref "C37") (pin "1") (pinfunction "1_1") (pintype "passive"))
      (node (ref "C46") (pin "1") (pinfunction "1_1") (pintype "passive"))
      (node (ref "TERM4") (pin "8") (pinfunction "8_8") (pintype "passive"))
    )
    (net (code "44") (name "/Feedback_11") (class "Default")
      (node (ref "C38") (pin "1") (pinfunction "1_1") (pintype "passive"))
      (node (ref "C47") (pin "1") (pinfunction "1_1") (pintype "passive"))
      (node (ref "TERM4") (pin "10") (pinfunction "10_10") (pintype "passive"))
    )
    (net (code "45") (name "/Feedback_12") (class "Default")
      (node (ref "C39") (pin "1") (pinfunction "1_1") (pintype "passive"))
      (node (ref "C48") (pin "1") (pinfunction "1_1") (pintype "passive"))
      (node (ref "TERM4") (pin "12") (pinfunction "12_12") (pintype "passive"))
    )
    (net (code "46") (name "/MCU_1") (class "Default")
      (node (ref "TERM3") (pin "1") (pinfunction "1_1") (pintype "passive"))
      (node (ref "TERM5") (pin "1") (pinfunction "1_1") (pintype "passive"))
    )
    (net (code "47") (name "/MCU_2") (class "Default")
      (node (ref "C9") (pin "2") (pinfunction "2_2") (pintype "passive"))
      (node (ref "R*2") (pin "2") (pinfunction "2_2") (pintype "passive"))
      (node (ref "TERM3") (pin "3") (pinfunction "3_3") (pintype "passive"))
      (node (ref "TERM5") (pin "2") (pinfunction "2_2") (pintype "passive"))
    )
    (net (code "48") (name "/MCU_3") (class "Default")
      (node (ref "C10") (pin "2") (pinfunction "2_2") (pintype "passive"))
      (node (ref "R*3") (pin "2") (pinfunction "2_2") (pintype "passive"))
      (node (ref "TERM3") (pin "5") (pinfunction "5_5") (pintype "passive"))
      (node (ref "TERM5") (pin "3") (pinfunction "3_3") (pintype "passive"))
    )
    (net (code "49") (name "/MCU_4") (class "Default")
      (node (ref "C11") (pin "2") (pinfunction "2_2") (pintype "passive"))
      (node (ref "R*4") (pin "2") (pinfunction "2_2") (pintype "passive"))
      (node (ref "TERM3") (pin "7") (pinfunction "7_7") (pintype "passive"))
      (node (ref "TERM5") (pin "4") (pinfunction "4_4") (pintype "passive"))
    )
    (net (code "50") (name "/MCU_5") (class "Default")
      (node (ref "C12") (pin "2") (pinfunction "2_2") (pintype "passive"))
      (node (ref "R*5") (pin "2") (pinfunction "2_2") (pintype "passive"))
      (node (ref "TERM3") (pin "9") (pinfunction "9_9") (pintype "passive"))
      (node (ref "TERM5") (pin "5") (pinfunction "5_5") (pintype "passive"))
    )
    (net (code "51") (name "/MCU_6") (class "Default")
      (node (ref "C25") (pin "2") (pinfunction "2_2") (pintype "passive"))
      (node (ref "R*6") (pin "2") (pinfunction "2_2") (pintype "passive"))
      (node (ref "TERM3") (pin "11") (pinfunction "11_11") (pintype "passive"))
      (node (ref "TERM5") (pin "6") (pinfunction "6_6") (pintype "passive"))
    )
    (net (code "52") (name "/MCU_7") (class "Default")
      (node (ref "C26") (pin "2") (pinfunction "2_2") (pintype "passive"))
      (node (ref "R*7") (pin "2") (pinfunction "2_2") (pintype "passive"))
      (node (ref "TERM4") (pin "1") (pinfunction "1_1") (pintype "passive"))
      (node (ref "TERM5") (pin "7") (pinfunction "7_7") (pintype "passive"))
    )
    (net (code "53") (name "/MCU_8") (class "Default")
      (node (ref "C27") (pin "2") (pinfunction "2_2") (pintype "passive"))
      (node (ref "R*8") (pin "2") (pinfunction "2_2") (pintype "passive"))
      (node (ref "TERM4") (pin "3") (pinfunction "3_3") (pintype "passive"))
      (node (ref "TERM5") (pin "8") (pinfunction "8_8") (pintype "passive"))
    )
    (net (code "54") (name "/MCU_9") (class "Default")
      (node (ref "C28") (pin "2") (pinfunction "2_2") (pintype "passive"))
      (node (ref "R*9") (pin "2") (pinfunction "2_2") (pintype "passive"))
      (node (ref "TERM4") (pin "5") (pinfunction "5_5") (pintype "passive"))
      (node (ref "TERM5") (pin "9") (pinfunction "9_9") (pintype "passive"))
    )
    (net (code "55") (name "/MCU_10") (class "Default")
      (node (ref "C40") (pin "2") (pinfunction "2_2") (pintype "passive"))
      (node (ref "R*10") (pin "2") (pinfunction "2_2") (pintype "passive"))
      (node (ref "TERM4") (pin "7") (pinfunction "7_7") (pintype "passive"))
      (node (ref "TERM5") (pin "10") (pinfunction "10_10") (pintype "passive"))
    )
    (net (code "56") (name "/MCU_11") (class "Default")
      (node (ref "C41") (pin "2") (pinfunction "2_2") (pintype "passive"))
      (node (ref "R*11") (pin "2") (pinfunction "2_2") (pintype "passive"))
      (node (ref "TERM4") (pin "9") (pinfunction "9_9") (pintype "passive"))
      (node (ref "TERM5") (pin "11") (pinfunction "11_11") (pintype "passive"))
    )
    (net (code "57") (name "/MCU_12") (class "Default")
      (node (ref "C42") (pin "2") (pinfunction "2_2") (pintype "passive"))
      (node (ref "R*12") (pin "2") (pinfunction "2_2") (pintype "passive"))
      (node (ref "TERM4") (pin "11") (pinfunction "11_11") (pintype "passive"))
      (node (ref "TERM5") (pin "12") (pinfunction "12_12") (pintype "passive"))
    )
    (net (code "58") (name "GND") (class "Default")
      (node (ref "C13") (pin "1") (pinfunction "1_1") (pintype "passive"))
      (node (ref "C14") (pin "1") (pinfunction "1_1") (pintype "passive"))
      (node (ref "C15") (pin "1") (pinfunction "1_1") (pintype "passive"))
      (node (ref "C17") (pin "1") (pinfunction "1_1") (pintype "passive"))
      (node (ref "C29") (pin "1") (pinfunction "1_1") (pintype "passive"))
      (node (ref "C30") (pin "1") (pinfunction "1_1") (pintype "passive"))
      (node (ref "C31") (pin "1") (pinfunction "1_1") (pintype "passive"))
      (node (ref "C33") (pin "1") (pinfunction "1_1") (pintype "passive"))
      (node (ref "C43") (pin "1") (pinfunction "1_1") (pintype "passive"))
      (node (ref "C44") (pin "1") (pinfunction "1_1") (pintype "passive"))
      (node (ref "C45") (pin "1") (pinfunction "1_1") (pintype "passive"))
      (node (ref "R14") (pin "1") (pinfunction "1_1") (pintype "passive"))
      (node (ref "R15") (pin "1") (pinfunction "1_1") (pintype "passive"))
      (node (ref "R16") (pin "1") (pinfunction "1_1") (pintype "passive"))
      (node (ref "R17") (pin "1") (pinfunction "1_1") (pintype "passive"))
      (node (ref "R18") (pin "1") (pinfunction "1_1") (pintype "passive"))
      (node (ref "R19") (pin "1") (pinfunction "1_1") (pintype "passive"))
      (node (ref "R20") (pin "1") (pinfunction "1_1") (pintype "passive"))
      (node (ref "R21") (pin "1") (pinfunction "1_1") (pintype "passive"))
      (node (ref "R30") (pin "1") (pinfunction "1_1") (pintype "passive"))
      (node (ref "R31") (pin "1") (pinfunction "1_1") (pintype "passive"))
      (node (ref "R32") (pin "1") (pinfunction "1_1") (pintype "passive"))
      (node (ref "R33") (pin "1") (pinfunction "1_1") (pintype "passive"))
      (node (ref "R34") (pin "1") (pinfunction "1_1") (pintype "passive"))
      (node (ref "R35") (pin "1") (pinfunction "1_1") (pintype "passive"))
      (node (ref "R36") (pin "1") (pinfunction "1_1") (pintype "passive"))
      (node (ref "R37") (pin "1") (pinfunction "1_1") (pintype "passive"))
      (node (ref "R44") (pin "1") (pinfunction "1_1") (pintype "passive"))
      (node (ref "R45") (pin "1") (pinfunction "1_1") (pintype "passive"))
      (node (ref "R46") (pin "1") (pinfunction "1_1") (pintype "passive"))
      (node (ref "R47") (pin "1") (pinfunction "1_1") (pintype "passive"))
      (node (ref "R48") (pin "1") (pinfunction "1_1") (pintype "passive"))
      (node (ref "R49") (pin "1") (pinfunction "1_1") (pintype "passive"))
    )
    (net (code "59") (name "VCC") (class "Default")
      (node (ref "R10") (pin "2") (pinfunction "2_2") (pintype "passive"))
      (node (ref "R11") (pin "2") (pinfunction "2_2") (pintype "passive"))
      (node (ref "R12") (pin "2") (pinfunction "2_2") (pintype "passive"))
      (node (ref "R13") (pin "2") (pinfunction "2_2") (pintype "passive"))
      (node (ref "R22") (pin "2") (pinfunction "2_2") (pintype "passive"))
      (node (ref "R23") (pin "2") (pinfunction "2_2") (pintype "passive"))
      (node (ref "R24") (pin "2") (pinfunction "2_2") (pintype "passive"))
      (node (ref "R25") (pin "2") (pinfunction "2_2") (pintype "passive"))
      (node (ref "R26") (pin "2") (pinfunction "2_2") (pintype "passive"))
      (node (ref "R27") (pin "2") (pinfunction "2_2") (pintype "passive"))
      (node (ref "R28") (pin "2") (pinfunction "2_2") (pintype "passive"))
      (node (ref "R29") (pin "2") (pinfunction "2_2") (pintype "passive"))
      (node (ref "R38") (pin "2") (pinfunction "2_2") (pintype "passive"))
      (node (ref "R39") (pin "2") (pinfunction "2_2") (pintype "passive"))
      (node (ref "R40") (pin "2") (pinfunction "2_2") (pintype "passive"))
      (node (ref "R41") (pin "2") (pinfunction "2_2") (pintype "passive"))
      (node (ref "R42") (pin "2") (pinfunction "2_2") (pintype "passive"))
      (node (ref "R43") (pin "2") (pinfunction "2_2") (pintype "passive"))
      (node (ref "R6") (pin "2") (pinfunction "2_2") (pintype "passive"))
      (node (ref "R7") (pin "2") (pinfunction "2_2") (pintype "passive"))
      (node (ref "R8") (pin "2") (pinfunction "2_2") (pintype "passive"))
      (node (ref "R9") (pin "2") (pinfunction "2_2") (pintype "passive"))
    )
  )
)
